# HMC830_CLK_DIST.net
KiCad netlist of a schematic drawn in Altium Designer
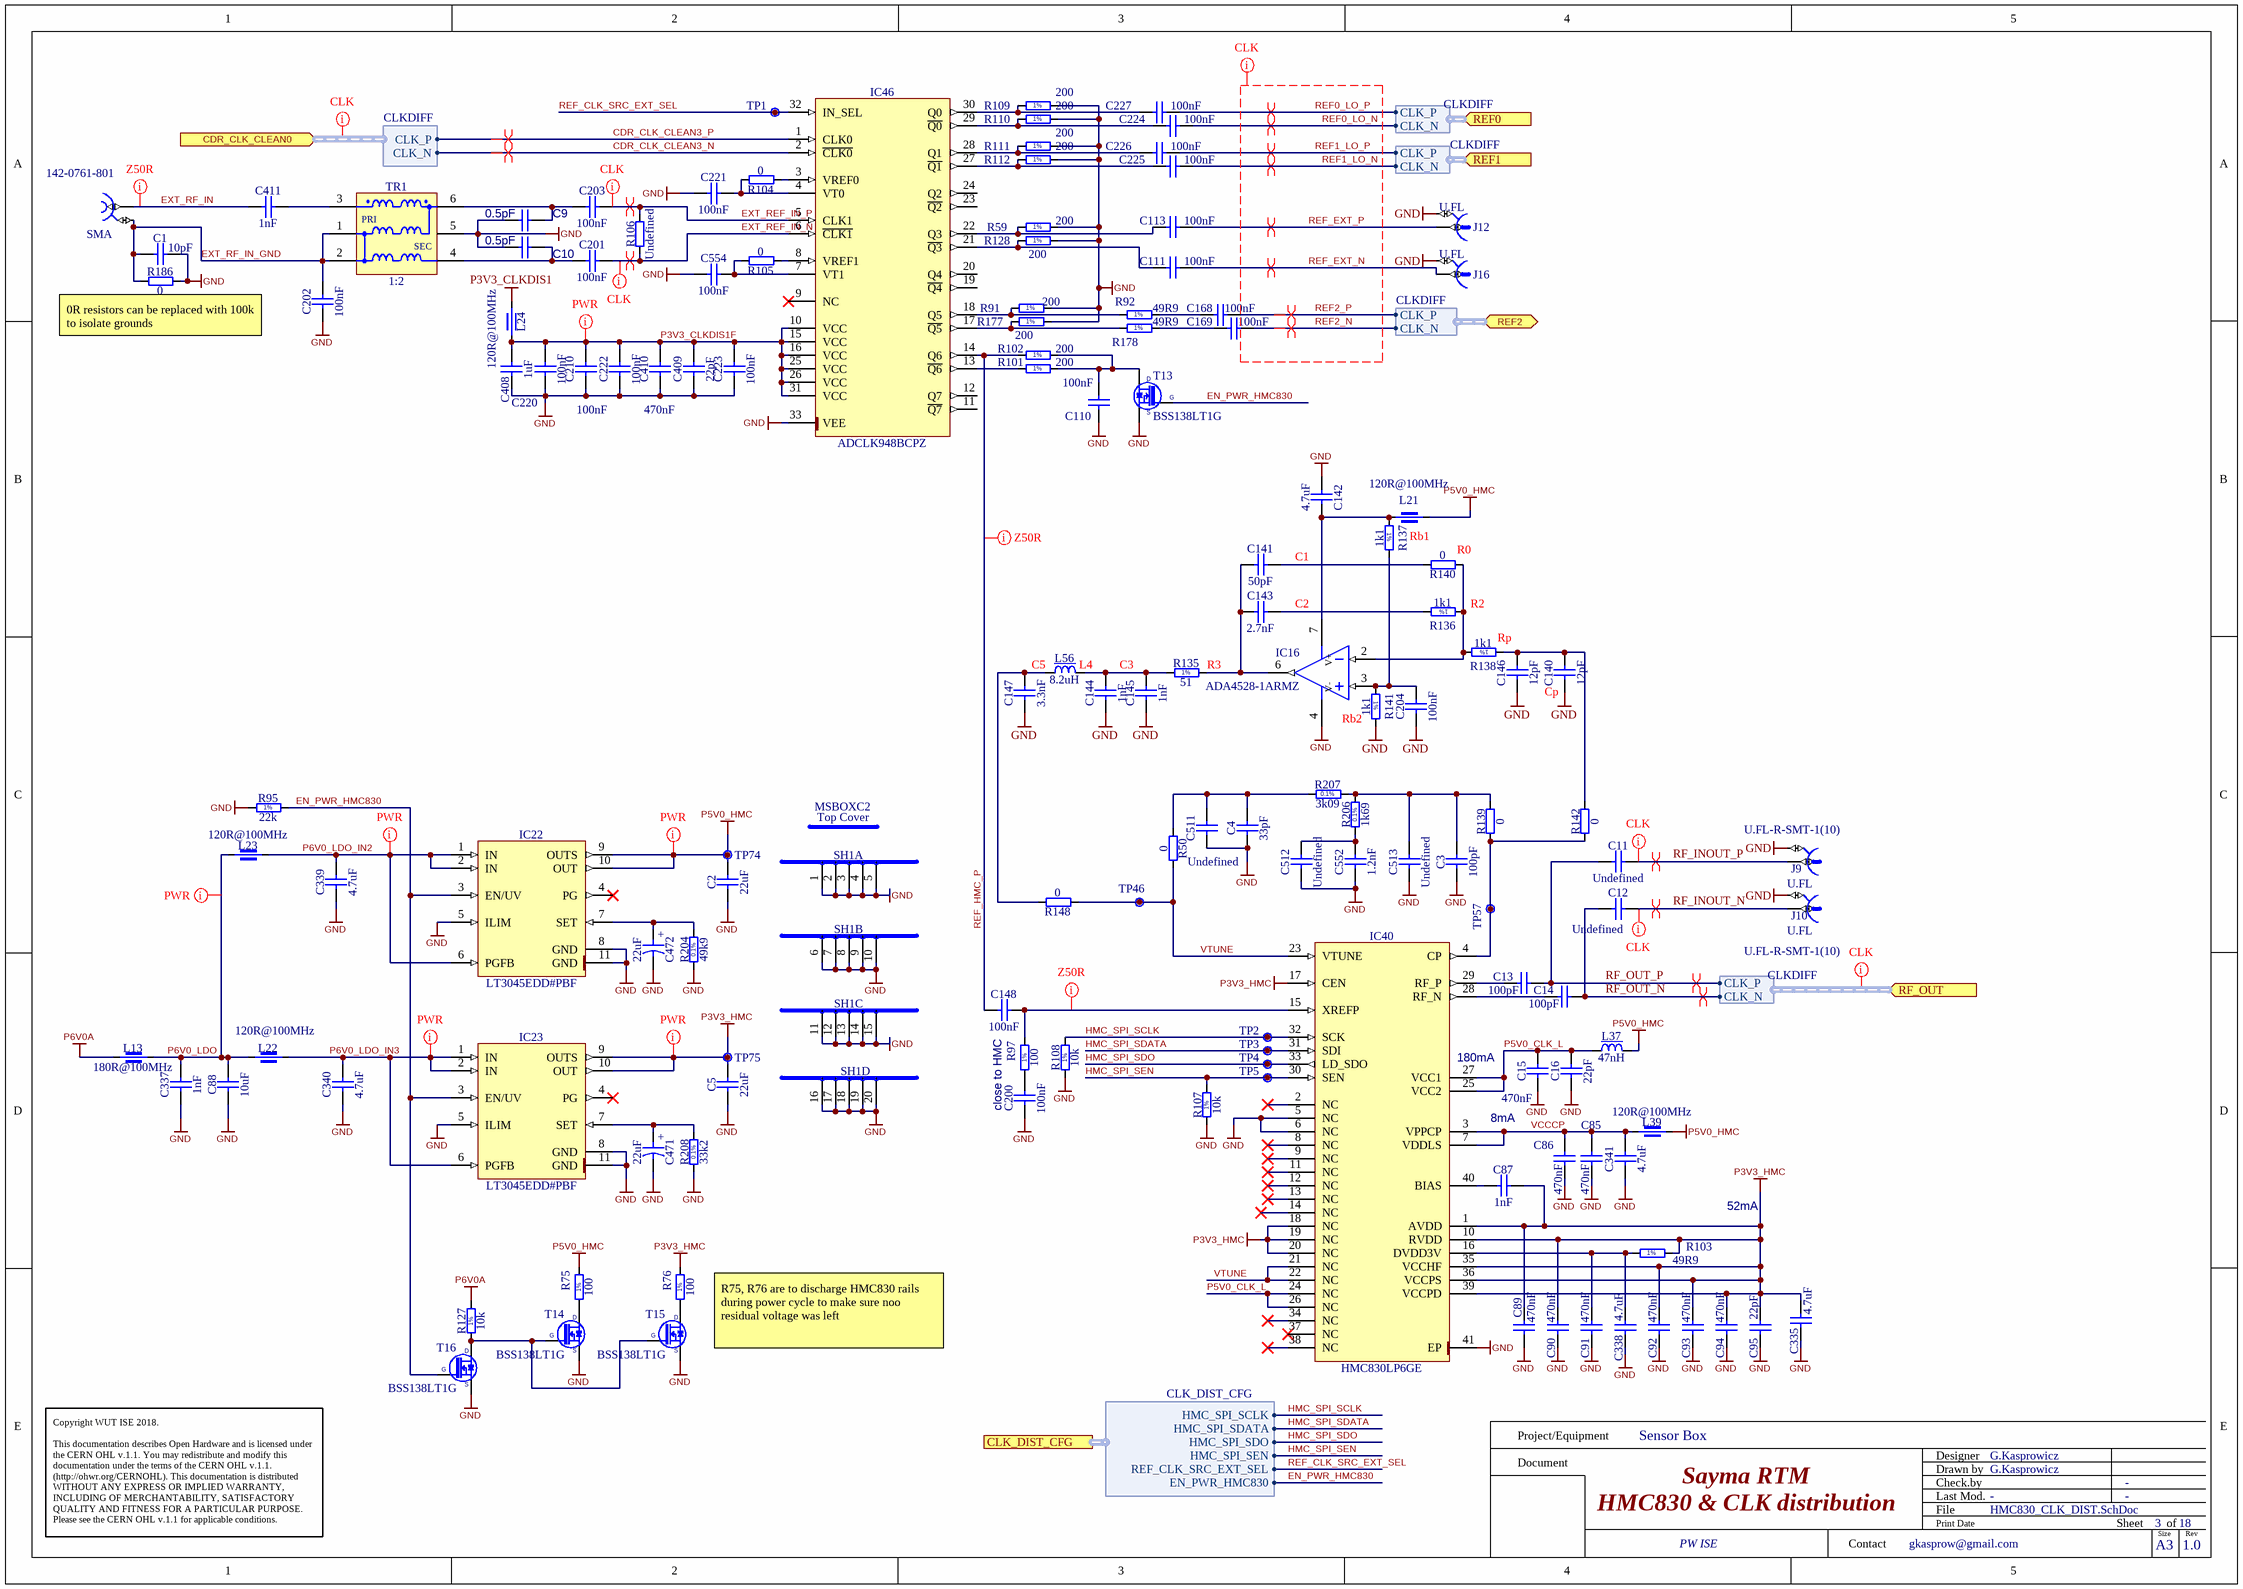
[diagram p0: HMC830_CLK_DIST.SchDoc]

(export (version "E")
  (design (tool "Eeschema 10.0.6"))
  (components
    (comp (ref "C1")
      (value "10pF")
      (footprint "CAPC1608X87N")
      (description "Non-polarised capacitor")
      (fields
        (field (name "MANUFACTURER PART NUMBER") "CC0603_10PF_50V_5%_NP0")
        (field (name "MANUFACTURER") "GENERIC")
        (field (name "AUTHOR") "CERN DEM JLC")
      )
      (libsource (lib "Capacitors") (part "Capacitor - non polarized"))
    )
    (comp (ref "C2")
      (value "22uF")
      (footprint "CAPC2012X135N")
      (description "Non-polarised capacitor")
      (fields
        (field (name "MANUFACTURER PART NUMBER") "CC0805_22UF_16V_10%_X5R")
        (field (name "MANUFACTURER") "GENERIC")
        (field (name "AUTHOR") "CERN DEM JLC")
      )
      (libsource (lib "Capacitors") (part "Capacitor - non polarized"))
    )
    (comp (ref "C3")
      (value "100pF")
      (footprint "CAPC1608X87N")
      (description "Non-polarised capacitor")
      (fields
        (field (name "MANUFACTURER PART NUMBER") "CC0603_100PF_50V_5%_NP0")
        (field (name "MANUFACTURER") "GENERIC")
        (field (name "AUTHOR") "CERN DEM JLC")
      )
      (libsource (lib "Capacitors") (part "Capacitor - non polarized"))
    )
    (comp (ref "C4")
      (value "33pF")
      (footprint "CAPC1608X87N")
      (description "Non-polarised capacitor")
      (fields
        (field (name "MANUFACTURER PART NUMBER") "CC0603_33PF_50V_5%_NP0")
        (field (name "MANUFACTURER") "GENERIC")
        (field (name "AUTHOR") "CERN DEM JLC")
      )
      (libsource (lib "Capacitors") (part "Capacitor - non polarized"))
    )
    (comp (ref "C5")
      (value "22uF")
      (footprint "CAPC2012X135N")
      (description "Non-polarised capacitor")
      (fields
        (field (name "MANUFACTURER PART NUMBER") "CC0805_22UF_16V_10%_X5R")
        (field (name "MANUFACTURER") "GENERIC")
        (field (name "AUTHOR") "CERN DEM JLC")
      )
      (libsource (lib "Capacitors") (part "Capacitor - non polarized"))
    )
    (comp (ref "C9")
      (value "0.5pF")
      (footprint "CAPC1005X55N")
      (fields
        (field (name "$$NOTCOMMONPROPERTY_GENERAL PART NUMBER") "CC0402_0.5PF_25V_0.25PF_C0G")
        (field (name "MANUFACTURER PART NUMBER") "CC0402_0.5PF_25V_0.05PF_C0G")
        (field (name "MANUFACTURER") "GENERIC")
      )
      (libsource (lib "altium-import") (part "root_0__*"))
    )
    (comp (ref "C10")
      (value "0.5pF")
      (footprint "CAPC1005X55N")
      (fields
        (field (name "$$NOTCOMMONPROPERTY_GENERAL PART NUMBER") "CC0402_0.5PF_25V_0.25PF_C0G")
        (field (name "MANUFACTURER PART NUMBER") "CC0402_0.5PF_25V_0.05PF_C0G")
        (field (name "MANUFACTURER") "GENERIC")
      )
      (libsource (lib "altium-import") (part "root_0__*"))
    )
    (comp (ref "C11")
      (value "Undefined")
      (footprint "CAPC1005X55N")
      (description "Non-polarised capacitor")
      (fields (field (name "PART NUMBER") "CC0402_NO-VALUE") (field (name "AUTHOR") "CERN DEM JLC"))
      (libsource (lib "Capacitors") (part "Capacitor - non polarized"))
    )
    (comp (ref "C12")
      (value "Undefined")
      (footprint "CAPC1005X55N")
      (description "Non-polarised capacitor")
      (fields (field (name "PART NUMBER") "CC0402_NO-VALUE") (field (name "AUTHOR") "CERN DEM JLC"))
      (libsource (lib "Capacitors") (part "Capacitor - non polarized"))
    )
    (comp (ref "C13")
      (value "100pF")
      (footprint "CAPC1608X87N")
      (description "Non-polarised capacitor")
      (fields
        (field (name "MANUFACTURER PART NUMBER") "CC0603_100PF_50V_5%_NP0")
        (field (name "MANUFACTURER") "GENERIC")
        (field (name "AUTHOR") "CERN DEM JLC")
      )
      (libsource (lib "Capacitors") (part "Capacitor - non polarized"))
    )
    (comp (ref "C14")
      (value "100pF")
      (footprint "CAPC1608X87N")
      (description "Non-polarised capacitor")
      (fields
        (field (name "MANUFACTURER PART NUMBER") "CC0603_100PF_50V_5%_NP0")
        (field (name "MANUFACTURER") "GENERIC")
        (field (name "AUTHOR") "CERN DEM JLC")
      )
      (libsource (lib "Capacitors") (part "Capacitor - non polarized"))
    )
    (comp (ref "C15")
      (value "470nF")
      (footprint "CAPC1005X55N")
      (description "Non-polarised capacitor")
      (fields
        (field (name "MANUFACTURER PART NUMBER") "CC0402_470NF_16V_10%_X5R")
        (field (name "MANUFACTURER") "GENERIC")
        (field (name "AUTHOR") "CERN DEM JLC")
      )
      (libsource (lib "Capacitors") (part "Capacitor - non polarized"))
    )
    (comp (ref "C16")
      (value "22pF")
      (footprint "CAPC1005X55N")
      (description "Non-polarised capacitor")
      (fields
        (field (name "MANUFACTURER PART NUMBER") "CC0402_22PF_50V_5%_C0G")
        (field (name "MANUFACTURER") "GENERIC")
        (field (name "AUTHOR") "CERN DEM JLC")
      )
      (libsource (lib "Capacitors") (part "Capacitor - non polarized"))
    )
    (comp (ref "C85")
      (value "470nF")
      (footprint "CAPC1005X55N")
      (description "Non-polarised capacitor")
      (fields
        (field (name "MANUFACTURER PART NUMBER") "CC0402_470NF_16V_10%_X5R")
        (field (name "MANUFACTURER") "GENERIC")
        (field (name "AUTHOR") "CERN DEM JLC")
      )
      (libsource (lib "Capacitors") (part "Capacitor - non polarized"))
    )
    (comp (ref "C86")
      (value "470nF")
      (footprint "CAPC1005X55N")
      (description "Non-polarised capacitor")
      (fields
        (field (name "MANUFACTURER PART NUMBER") "CC0402_470NF_16V_10%_X5R")
        (field (name "MANUFACTURER") "GENERIC")
        (field (name "AUTHOR") "CERN DEM JLC")
      )
      (libsource (lib "Capacitors") (part "Capacitor - non polarized"))
    )
    (comp (ref "C87")
      (value "1nF")
      (footprint "CAPC1005X55N")
      (description "Non-polarised capacitor")
      (fields
        (field (name "MANUFACTURER PART NUMBER") "CC0402_1NF_50V_10%_X7R")
        (field (name "MANUFACTURER") "GENERIC")
        (field (name "AUTHOR") "CERN DEM JLC")
      )
      (libsource (lib "Capacitors") (part "Capacitor - non polarized"))
    )
    (comp (ref "C88")
      (value "10uF")
      (footprint "CAPC3216X180N")
      (description "Non-polarised capacitor")
      (fields
        (field (name "MANUFACTURER PART NUMBER") "CC1206_10uF_25V_10%_X7R")
        (field (name "MANUFACTURER") "GENERIC")
        (field (name "AUTHOR") "CERN DEM JLC")
      )
      (libsource (lib "Capacitors") (part "Capacitor - non polarized"))
    )
    (comp (ref "C89")
      (value "470nF")
      (footprint "CAPC1005X55N")
      (description "Non-polarised capacitor")
      (fields
        (field (name "MANUFACTURER PART NUMBER") "CC0402_470NF_16V_10%_X5R")
        (field (name "MANUFACTURER") "GENERIC")
        (field (name "AUTHOR") "CERN DEM JLC")
      )
      (libsource (lib "Capacitors") (part "Capacitor - non polarized"))
    )
    (comp (ref "C90")
      (value "470nF")
      (footprint "CAPC1005X55N")
      (description "Non-polarised capacitor")
      (fields
        (field (name "MANUFACTURER PART NUMBER") "CC0402_470NF_16V_10%_X5R")
        (field (name "MANUFACTURER") "GENERIC")
        (field (name "AUTHOR") "CERN DEM JLC")
      )
      (libsource (lib "Capacitors") (part "Capacitor - non polarized"))
    )
    (comp (ref "C91")
      (value "470nF")
      (footprint "CAPC1005X55N")
      (description "Non-polarised capacitor")
      (fields
        (field (name "MANUFACTURER PART NUMBER") "CC0402_470NF_16V_10%_X5R")
        (field (name "MANUFACTURER") "GENERIC")
        (field (name "AUTHOR") "CERN DEM JLC")
      )
      (libsource (lib "Capacitors") (part "Capacitor - non polarized"))
    )
    (comp (ref "C92")
      (value "470nF")
      (footprint "CAPC1005X55N")
      (description "Non-polarised capacitor")
      (fields
        (field (name "MANUFACTURER PART NUMBER") "CC0402_470NF_16V_10%_X5R")
        (field (name "MANUFACTURER") "GENERIC")
        (field (name "AUTHOR") "CERN DEM JLC")
      )
      (libsource (lib "Capacitors") (part "Capacitor - non polarized"))
    )
    (comp (ref "C93")
      (value "470nF")
      (footprint "CAPC1005X55N")
      (description "Non-polarised capacitor")
      (fields
        (field (name "MANUFACTURER PART NUMBER") "CC0402_470NF_16V_10%_X5R")
        (field (name "MANUFACTURER") "GENERIC")
        (field (name "AUTHOR") "CERN DEM JLC")
      )
      (libsource (lib "Capacitors") (part "Capacitor - non polarized"))
    )
    (comp (ref "C94")
      (value "470nF")
      (footprint "CAPC1005X55N")
      (description "Non-polarised capacitor")
      (fields
        (field (name "MANUFACTURER PART NUMBER") "CC0402_470NF_16V_10%_X5R")
        (field (name "MANUFACTURER") "GENERIC")
        (field (name "AUTHOR") "CERN DEM JLC")
      )
      (libsource (lib "Capacitors") (part "Capacitor - non polarized"))
    )
    (comp (ref "C95")
      (value "22pF")
      (footprint "CAPC1005X55N")
      (description "Non-polarised capacitor")
      (fields
        (field (name "MANUFACTURER PART NUMBER") "CC0402_22PF_50V_5%_C0G")
        (field (name "MANUFACTURER") "GENERIC")
        (field (name "AUTHOR") "CERN DEM JLC")
      )
      (libsource (lib "Capacitors") (part "Capacitor - non polarized"))
    )
    (comp (ref "C110")
      (value "100nF")
      (footprint "CAPC0603X33N")
      (description "Non-polarised capacitor")
      (fields
        (field (name "MANUFACTURER PART NUMBER") "CC0201_100NF_6.3V_10%_X5R")
        (field (name "MANUFACTURER") "GENERIC")
        (field (name "AUTHOR") "CERN DEM JLC")
      )
      (libsource (lib "Capacitors") (part "Capacitor - non polarized"))
    )
    (comp (ref "C111")
      (value "100nF")
      (footprint "CAPC0603X33N")
      (description "Non-polarised capacitor")
      (fields
        (field (name "MANUFACTURER PART NUMBER") "CC0201_100NF_6.3V_10%_X5R")
        (field (name "MANUFACTURER") "GENERIC")
        (field (name "AUTHOR") "CERN DEM JLC")
      )
      (libsource (lib "Capacitors") (part "Capacitor - non polarized"))
    )
    (comp (ref "C113")
      (value "100nF")
      (footprint "CAPC0603X33N")
      (description "Non-polarised capacitor")
      (fields
        (field (name "MANUFACTURER PART NUMBER") "CC0201_100NF_6.3V_10%_X5R")
        (field (name "MANUFACTURER") "GENERIC")
        (field (name "AUTHOR") "CERN DEM JLC")
      )
      (libsource (lib "Capacitors") (part "Capacitor - non polarized"))
    )
    (comp (ref "C140")
      (value "12pF")
      (footprint "CAPC1608X87N")
      (description "Non-polarised capacitor")
      (fields
        (field (name "PART NUMBER") "CC0603_12PF_50V_5%_NP0")
        (field (name "VOLTAGE") "50V")
        (field (name "AUTHOR") "CERN DEM JLC")
      )
      (libsource (lib "Capacitors") (part "Capacitor - non polarized"))
    )
    (comp (ref "C141")
      (value "50pF")
      (footprint "CAPC1608X90N")
      (description "Non-polarised capacitor")
      (fields
        (field (name "PART NUMBER") "CC0603_50PF_50V_5%_NP0")
        (field (name "VOLTAGE") "50V")
        (field (name "AUTHOR") "CERN DEM JLC")
      )
      (libsource (lib "Capacitors") (part "Capacitor - non polarized"))
    )
    (comp (ref "C142")
      (value "4.7uF")
      (footprint "CAPC1608X90N")
      (description "Non-polarised capacitor")
      (fields
        (field (name "MANUFACTURER PART NUMBER") "CC0603_4.7UF_25V_10%_X5R")
        (field (name "MANUFACTURER") "GENERIC")
        (field (name "AUTHOR") "CERN DEM JLC")
      )
      (libsource (lib "Capacitors") (part "Capacitor - non polarized"))
    )
    (comp (ref "C143")
      (value "2.7nF")
      (footprint "CAPC3216X140N")
      (description "Non-polarised capacitor")
      (fields
        (field (name "PART NUMBER") "CC1206_2.7NF_100V_1%_NP0")
        (field (name "VOLTAGE") "100V")
        (field (name "AUTHOR") "CERN DEM JLC")
      )
      (libsource (lib "Capacitors") (part "Capacitor - non polarized"))
    )
    (comp (ref "C144")
      (value "1nF")
      (footprint "CAPC1608X90N")
      (description "Non-polarised capacitor")
      (fields
        (field (name "PART NUMBER") "CC0603_1NF_50V_1%_NP0")
        (field (name "VOLTAGE") "50V")
        (field (name "AUTHOR") "CERN DEM JLC")
      )
      (libsource (lib "Capacitors") (part "Capacitor - non polarized"))
    )
    (comp (ref "C145")
      (value "1nF")
      (footprint "CAPC1608X90N")
      (description "Non-polarised capacitor")
      (fields
        (field (name "PART NUMBER") "CC0603_1NF_50V_1%_NP0")
        (field (name "VOLTAGE") "50V")
        (field (name "AUTHOR") "CERN DEM JLC")
      )
      (libsource (lib "Capacitors") (part "Capacitor - non polarized"))
    )
    (comp (ref "C146")
      (value "12pF")
      (footprint "CAPC1608X87N")
      (description "Non-polarised capacitor")
      (fields
        (field (name "PART NUMBER") "CC0603_12PF_50V_5%_NP0")
        (field (name "VOLTAGE") "50V")
        (field (name "AUTHOR") "CERN DEM JLC")
      )
      (libsource (lib "Capacitors") (part "Capacitor - non polarized"))
    )
    (comp (ref "C147")
      (value "3.3nF")
      (footprint "CAPC1608X87N")
      (description "Non-polarised capacitor")
      (fields
        (field (name "PART NUMBER") "CC0603_3.3NF_50V_10%_X7R")
        (field (name "VOLTAGE") "50V")
        (field (name "AUTHOR") "CERN DEM JLC")
      )
      (libsource (lib "Capacitors") (part "Capacitor - non polarized"))
    )
    (comp (ref "C148")
      (value "100nF")
      (footprint "CAPC0603X33N")
      (description "Non-polarised capacitor")
      (fields
        (field (name "MANUFACTURER PART NUMBER") "CC0201_100NF_6.3V_10%_X5R")
        (field (name "MANUFACTURER") "GENERIC")
        (field (name "AUTHOR") "CERN DEM JLC")
      )
      (libsource (lib "Capacitors") (part "Capacitor - non polarized"))
    )
    (comp (ref "C168")
      (value "100nF")
      (footprint "CAPC0603X33N")
      (description "Non-polarised capacitor")
      (fields
        (field (name "MANUFACTURER PART NUMBER") "CC0201_100NF_6.3V_10%_X5R")
        (field (name "MANUFACTURER") "GENERIC")
        (field (name "AUTHOR") "CERN DEM JLC")
      )
      (libsource (lib "Capacitors") (part "Capacitor - non polarized"))
    )
    (comp (ref "C169")
      (value "100nF")
      (footprint "CAPC0603X33N")
      (description "Non-polarised capacitor")
      (fields
        (field (name "MANUFACTURER PART NUMBER") "CC0201_100NF_6.3V_10%_X5R")
        (field (name "MANUFACTURER") "GENERIC")
        (field (name "AUTHOR") "CERN DEM JLC")
      )
      (libsource (lib "Capacitors") (part "Capacitor - non polarized"))
    )
    (comp (ref "C200")
      (value "100nF")
      (footprint "CAPC0603X33N")
      (description "Non-polarised capacitor")
      (fields
        (field (name "MANUFACTURER PART NUMBER") "CC0201_100NF_6.3V_10%_X5R")
        (field (name "MANUFACTURER") "GENERIC")
        (field (name "AUTHOR") "CERN DEM JLC")
      )
      (libsource (lib "Capacitors") (part "Capacitor - non polarized"))
    )
    (comp (ref "C201")
      (value "100nF")
      (footprint "CAPC0603X33N")
      (description "Non-polarised capacitor")
      (fields
        (field (name "MANUFACTURER PART NUMBER") "CC0201_100NF_6.3V_10%_X5R")
        (field (name "MANUFACTURER") "GENERIC")
        (field (name "AUTHOR") "CERN DEM JLC")
      )
      (libsource (lib "Capacitors") (part "Capacitor - non polarized"))
    )
    (comp (ref "C202")
      (value "100nF")
      (footprint "CAPC0603X33N")
      (description "Non-polarised capacitor")
      (fields
        (field (name "MANUFACTURER PART NUMBER") "CC0201_100NF_6.3V_10%_X5R")
        (field (name "MANUFACTURER") "GENERIC")
        (field (name "AUTHOR") "CERN DEM JLC")
      )
      (libsource (lib "Capacitors") (part "Capacitor - non polarized"))
    )
    (comp (ref "C203")
      (value "100nF")
      (footprint "CAPC0603X33N")
      (description "Non-polarised capacitor")
      (fields
        (field (name "MANUFACTURER PART NUMBER") "CC0201_100NF_6.3V_10%_X5R")
        (field (name "MANUFACTURER") "GENERIC")
        (field (name "AUTHOR") "CERN DEM JLC")
      )
      (libsource (lib "Capacitors") (part "Capacitor - non polarized"))
    )
    (comp (ref "C204")
      (value "100nF")
      (footprint "CAPC0603X33N")
      (description "Non-polarised capacitor")
      (fields
        (field (name "MANUFACTURER PART NUMBER") "CC0201_100NF_6.3V_10%_X5R")
        (field (name "MANUFACTURER") "GENERIC")
        (field (name "AUTHOR") "CERN DEM JLC")
      )
      (libsource (lib "Capacitors") (part "Capacitor - non polarized"))
    )
    (comp (ref "C210")
      (value "100nF")
      (footprint "CAPC0603X33N")
      (description "Non-polarised capacitor")
      (fields
        (field (name "MANUFACTURER PART NUMBER") "CC0201_100NF_6.3V_10%_X5R")
        (field (name "MANUFACTURER") "GENERIC")
        (field (name "AUTHOR") "CERN DEM JLC")
      )
      (libsource (lib "Capacitors") (part "Capacitor - non polarized"))
    )
    (comp (ref "C220")
      (value "100nF")
      (footprint "CAPC0603X33N")
      (description "Non-polarised capacitor")
      (fields
        (field (name "MANUFACTURER PART NUMBER") "CC0201_100NF_6.3V_10%_X5R")
        (field (name "MANUFACTURER") "GENERIC")
        (field (name "AUTHOR") "CERN DEM JLC")
      )
      (libsource (lib "Capacitors") (part "Capacitor - non polarized"))
    )
    (comp (ref "C221")
      (value "100nF")
      (footprint "CAPC0603X33N")
      (description "Non-polarised capacitor")
      (fields
        (field (name "MANUFACTURER PART NUMBER") "CC0201_100NF_6.3V_10%_X5R")
        (field (name "MANUFACTURER") "GENERIC")
        (field (name "AUTHOR") "CERN DEM JLC")
      )
      (libsource (lib "Capacitors") (part "Capacitor - non polarized"))
    )
    (comp (ref "C222")
      (value "100nF")
      (footprint "CAPC0603X33N")
      (description "Non-polarised capacitor")
      (fields
        (field (name "MANUFACTURER PART NUMBER") "CC0201_100NF_6.3V_10%_X5R")
        (field (name "MANUFACTURER") "GENERIC")
        (field (name "AUTHOR") "CERN DEM JLC")
      )
      (libsource (lib "Capacitors") (part "Capacitor - non polarized"))
    )
    (comp (ref "C223")
      (value "100nF")
      (footprint "CAPC0603X33N")
      (description "Non-polarised capacitor")
      (fields
        (field (name "MANUFACTURER PART NUMBER") "CC0201_100NF_6.3V_10%_X5R")
        (field (name "MANUFACTURER") "GENERIC")
        (field (name "AUTHOR") "CERN DEM JLC")
      )
      (libsource (lib "Capacitors") (part "Capacitor - non polarized"))
    )
    (comp (ref "C224")
      (value "100nF")
      (footprint "CAPC0603X33N")
      (description "Non-polarised capacitor")
      (fields
        (field (name "MANUFACTURER PART NUMBER") "CC0201_100NF_6.3V_10%_X5R")
        (field (name "MANUFACTURER") "GENERIC")
        (field (name "AUTHOR") "CERN DEM JLC")
      )
      (libsource (lib "Capacitors") (part "Capacitor - non polarized"))
    )
    (comp (ref "C225")
      (value "100nF")
      (footprint "CAPC0603X33N")
      (description "Non-polarised capacitor")
      (fields
        (field (name "MANUFACTURER PART NUMBER") "CC0201_100NF_6.3V_10%_X5R")
        (field (name "MANUFACTURER") "GENERIC")
        (field (name "AUTHOR") "CERN DEM JLC")
      )
      (libsource (lib "Capacitors") (part "Capacitor - non polarized"))
    )
    (comp (ref "C226")
      (value "100nF")
      (footprint "CAPC0603X33N")
      (description "Non-polarised capacitor")
      (fields
        (field (name "MANUFACTURER PART NUMBER") "CC0201_100NF_6.3V_10%_X5R")
        (field (name "MANUFACTURER") "GENERIC")
        (field (name "AUTHOR") "CERN DEM JLC")
      )
      (libsource (lib "Capacitors") (part "Capacitor - non polarized"))
    )
    (comp (ref "C227")
      (value "100nF")
      (footprint "CAPC0603X33N")
      (description "Non-polarised capacitor")
      (fields
        (field (name "MANUFACTURER PART NUMBER") "CC0201_100NF_6.3V_10%_X5R")
        (field (name "MANUFACTURER") "GENERIC")
        (field (name "AUTHOR") "CERN DEM JLC")
      )
      (libsource (lib "Capacitors") (part "Capacitor - non polarized"))
    )
    (comp (ref "C335")
      (value "4.7uF")
      (footprint "CAPC1608X90N")
      (description "Non-polarised capacitor")
      (fields
        (field (name "MANUFACTURER PART NUMBER") "CC0603_4.7UF_25V_10%_X5R")
        (field (name "MANUFACTURER") "GENERIC")
        (field (name "AUTHOR") "CERN DEM JLC")
      )
      (libsource (lib "Capacitors") (part "Capacitor - non polarized"))
    )
    (comp (ref "C337")
      (value "1nF")
      (footprint "CAPC1608X90N")
      (description "Non-polarised capacitor")
      (fields
        (field (name "MANUFACTURER PART NUMBER") "CC0603_1NF_50V_5%_NP0")
        (field (name "MANUFACTURER") "GENERIC")
        (field (name "AUTHOR") "CERN DEM JLC")
      )
      (libsource (lib "Capacitors") (part "Capacitor - non polarized"))
    )
    (comp (ref "C338")
      (value "4.7uF")
      (footprint "CAPC1608X90N")
      (description "Non-polarised capacitor")
      (fields
        (field (name "MANUFACTURER PART NUMBER") "CC0603_4.7UF_25V_10%_X5R")
        (field (name "MANUFACTURER") "GENERIC")
        (field (name "AUTHOR") "CERN DEM JLC")
      )
      (libsource (lib "Capacitors") (part "Capacitor - non polarized"))
    )
    (comp (ref "C339")
      (value "4.7uF")
      (footprint "CAPC1608X90N")
      (description "Non-polarised capacitor")
      (fields
        (field (name "MANUFACTURER PART NUMBER") "CC0603_4.7UF_25V_10%_X5R")
        (field (name "MANUFACTURER") "GENERIC")
        (field (name "AUTHOR") "CERN DEM JLC")
      )
      (libsource (lib "Capacitors") (part "Capacitor - non polarized"))
    )
    (comp (ref "C340")
      (value "4.7uF")
      (footprint "CAPC1608X90N")
      (description "Non-polarised capacitor")
      (fields
        (field (name "MANUFACTURER PART NUMBER") "CC0603_4.7UF_25V_10%_X5R")
        (field (name "MANUFACTURER") "GENERIC")
        (field (name "AUTHOR") "CERN DEM JLC")
      )
      (libsource (lib "Capacitors") (part "Capacitor - non polarized"))
    )
    (comp (ref "C341")
      (value "4.7uF")
      (footprint "CAPC1608X90N")
      (description "Non-polarised capacitor")
      (fields
        (field (name "MANUFACTURER PART NUMBER") "CC0603_4.7UF_25V_10%_X5R")
        (field (name "MANUFACTURER") "GENERIC")
        (field (name "AUTHOR") "CERN DEM JLC")
      )
      (libsource (lib "Capacitors") (part "Capacitor - non polarized"))
    )
    (comp (ref "C408")
      (value "1uF")
      (footprint "CAPC1005X55N")
      (description "Non-polarised capacitor")
      (fields
        (field (name "MANUFACTURER PART NUMBER") "CC0402_1UF_16V_10%_X5R")
        (field (name "MANUFACTURER") "GENERIC")
        (field (name "AUTHOR") "CERN DEM JLC")
      )
      (libsource (lib "Capacitors") (part "Capacitor - non polarized"))
    )
    (comp (ref "C409")
      (value "22pF")
      (footprint "CAPC1005X55N")
      (description "Non-polarised capacitor")
      (fields
        (field (name "MANUFACTURER PART NUMBER") "CC0402_22PF_50V_5%_C0G")
        (field (name "MANUFACTURER") "GENERIC")
        (field (name "AUTHOR") "CERN DEM JLC")
      )
      (libsource (lib "Capacitors") (part "Capacitor - non polarized"))
    )
    (comp (ref "C410")
      (value "470nF")
      (footprint "CAPC1005X55N")
      (description "Non-polarised capacitor")
      (fields
        (field (name "MANUFACTURER PART NUMBER") "CC0402_470NF_16V_10%_X5R")
        (field (name "MANUFACTURER") "GENERIC")
        (field (name "AUTHOR") "CERN DEM JLC")
      )
      (libsource (lib "Capacitors") (part "Capacitor - non polarized"))
    )
    (comp (ref "C411")
      (value "1nF")
      (footprint "CAPC1005X55N")
      (description "Non-polarised capacitor")
      (fields
        (field (name "MANUFACTURER PART NUMBER") "CC0402_1NF_50V_10%_X7R")
        (field (name "MANUFACTURER") "GENERIC")
        (field (name "AUTHOR") "CERN DEM JLC")
      )
      (libsource (lib "Capacitors") (part "Capacitor - non polarized"))
    )
    (comp (ref "C471")
      (value "22uF")
      (footprint "CAPMP3216X180N")
      (description "Polarised capacitor")
      (fields
        (field (name "MANUFACTURER PART NUMBER") "CTE3216-18_22UF_6.3V_10%_LESR0900")
        (field (name "MANUFACTURER") "GENERIC")
        (field (name "AUTHOR") "CERN DEM JLC")
      )
      (libsource (lib "Capacitors") (part "Capacitor - polarized"))
    )
    (comp (ref "C472")
      (value "22uF")
      (footprint "CAPMP3216X180N")
      (description "Polarised capacitor")
      (fields
        (field (name "MANUFACTURER PART NUMBER") "CTE3216-18_22UF_6.3V_10%_LESR0900")
        (field (name "MANUFACTURER") "GENERIC")
        (field (name "AUTHOR") "CERN DEM JLC")
      )
      (libsource (lib "Capacitors") (part "Capacitor - polarized"))
    )
    (comp (ref "C511")
      (value "Undefined")
      (footprint "CAPC2012X135N")
      (description "Non-polarised capacitor")
      (fields
        (field (name "MANUFACTURER PART NUMBER") "CC0805_NO-VALUE")
        (field (name "AUTHOR") "CERN DEM JLC")
      )
      (libsource (lib "Capacitors") (part "Capacitor - non polarized"))
    )
    (comp (ref "C512")
      (value "Undefined")
      (footprint "CAPC2012X135N")
      (description "Non-polarised capacitor")
      (fields
        (field (name "MANUFACTURER PART NUMBER") "CC0805_NO-VALUE")
        (field (name "AUTHOR") "CERN DEM JLC")
      )
      (libsource (lib "Capacitors") (part "Capacitor - non polarized"))
    )
    (comp (ref "C513")
      (value "Undefined")
      (footprint "CAPC2012X135N")
      (description "Non-polarised capacitor")
      (fields
        (field (name "MANUFACTURER PART NUMBER") "CC0805_NO-VALUE")
        (field (name "AUTHOR") "CERN DEM JLC")
      )
      (libsource (lib "Capacitors") (part "Capacitor - non polarized"))
    )
    (comp (ref "C552")
      (value "1.2nF")
      (footprint "CAPC3216X140N")
      (description "Non-polarised capacitor")
      (fields
        (field (name "MANUFACTURER PART NUMBER") "CC1206_1.2NF_50V_5%_NP0")
        (field (name "MANUFACTURER") "GENERIC")
        (field (name "AUTHOR") "CERN DEM JLC")
      )
      (libsource (lib "Capacitors") (part "Capacitor - non polarized"))
    )
    (comp (ref "C554")
      (value "100nF")
      (footprint "CAPC0603X33N")
      (description "Non-polarised capacitor")
      (fields
        (field (name "MANUFACTURER PART NUMBER") "CC0201_100NF_6.3V_10%_X5R")
        (field (name "MANUFACTURER") "GENERIC")
        (field (name "AUTHOR") "CERN DEM JLC")
      )
      (libsource (lib "Capacitors") (part "Capacitor - non polarized"))
    )
    (comp (ref "IC16")
      (value "ADA4528-1ARMZ")
      (footprint "SOP65P490X110-8N")
      (description "Operational Amplifier")
      (fields (field (name "MANUFACTURER") "ANALOG DEVICES") (field (name "AUTHOR") "CERN DEM JLC"))
      (libsource (lib "ICs And Semiconductors") (part "Operational Amplifier Type1"))
    )
    (comp (ref "IC22")
      (value "LT3045EDD#PBF")
      (footprint "SON50P300X300X80-11N-R175X248")
      (description "20V, 500mA, Ultralow Noise, Ultrahigh PSRR Linear Regulator")
      (fields (field (name "MANUFACTURER") "LINEAR TECHNOLOGY") (field (name "AUTHOR") "CERN DEM JLC"))
      (libsource (lib "ICs And Semiconductors") (part "LT3045EDD"))
    )
    (comp (ref "IC23")
      (value "LT3045EDD#PBF")
      (footprint "SON50P300X300X80-11N-R175X248")
      (description "20V, 500mA, Ultralow Noise, Ultrahigh PSRR Linear Regulator")
      (fields (field (name "MANUFACTURER") "LINEAR TECHNOLOGY") (field (name "AUTHOR") "CERN DEM JLC"))
      (libsource (lib "ICs And Semiconductors") (part "LT3045EDD"))
    )
    (comp (ref "IC40")
      (value "HMC830LP6GE")
      (footprint "QFN50P600X600X90-41N-S475")
      (description "Fractional-N PLL With Integrated VCO, 25 to 3000MHz")
      (fields (field (name "MANUFACTURER") "HITTITE MICROWAVE CORP") (field (name "AUTHOR") "CERN DEM JMW"))
      (libsource (lib "ICs And Semiconductors") (part "HMC830LP6GE"))
    )
    (comp (ref "IC46")
      (value "ADCLK948BCPZ")
      (footprint "QFN50P500X500X80-33N-S285")
      (description "Two Selectable Inputs, 8 LVPECL Outputs, SiGe Clock Fanout Buffer")
      (fields (field (name "MANUFACTURER") "ANALOG DEVICES") (field (name "AUTHOR") "CERN DEM MR"))
      (libsource (lib "ICs And Semiconductors") (part "ADCLK948"))
    )
    (comp (ref "J4")
      (value "SMA")
      (footprint "CINCH_142-0761-801")
      (fields
        (field (name "FAMILY") "SMA")
        (field (name "MANUFACTURER PART NUMBER") "142-0761-801")
        (field (name "MANUFACTURER") "CINCH CONNECTIVITY")
        (field (name "PART NUMBER") "CINCH_142-0761-801")
        (field (name "AUTHOR") "CERN DEM JLC")
      )
      (libsource (lib "Connectors") (part "Coax_1Female_1Shield"))
    )
    (comp (ref "J9")
      (value "U.FL")
      (footprint "HIROSE_U.FL-R-SMT-1(10)")
      (fields
        (field (name "FAMILY") "U.FL")
        (field (name "MANUFACTURER PART NUMBER") "U.FL-R-SMT-1(10)")
        (field (name "MANUFACTURER") "HIROSE (HRS)")
        (field (name "PART NUMBER") "HIROSE_U.FL-R-SMT-1(10)")
        (field (name "AUTHOR") "CERN DEM JLC")
      )
      (libsource (lib "Connectors") (part "Coax_1Male_1Shield"))
    )
    (comp (ref "J10")
      (value "U.FL")
      (footprint "HIROSE_U.FL-R-SMT-1(10)")
      (fields
        (field (name "FAMILY") "U.FL")
        (field (name "MANUFACTURER PART NUMBER") "U.FL-R-SMT-1(10)")
        (field (name "MANUFACTURER") "HIROSE (HRS)")
        (field (name "PART NUMBER") "HIROSE_U.FL-R-SMT-1(10)")
        (field (name "AUTHOR") "CERN DEM JLC")
      )
      (libsource (lib "Connectors") (part "Coax_1Male_1Shield"))
    )
    (comp (ref "J12")
      (value "U.FL")
      (footprint "HIROSE_U.FL-R-SMT-1(10)")
      (fields
        (field (name "MANUFACTURER PART NUMBER") "U.FL-R-SMT-1(10)")
        (field (name "MANUFACTURER") "HIROSE (HRS)")
        (field (name "PART NUMBER") "HIROSE_U.FL-R-SMT-1(10)")
        (field (name "AUTHOR") "CERN DEM JLC")
      )
      (libsource (lib "Connectors") (part "Coax_1Male_1Shield"))
    )
    (comp (ref "J16")
      (value "U.FL")
      (footprint "HIROSE_U.FL-R-SMT-1(10)")
      (fields
        (field (name "MANUFACTURER PART NUMBER") "U.FL-R-SMT-1(10)")
        (field (name "MANUFACTURER") "HIROSE (HRS)")
        (field (name "PART NUMBER") "HIROSE_U.FL-R-SMT-1(10)")
        (field (name "AUTHOR") "CERN DEM JLC")
      )
      (libsource (lib "Connectors") (part "Coax_1Male_1Shield"))
    )
    (comp (ref "L13")
      (value "180R@100MHz")
      (footprint "INDC4516X180N")
      (fields
        (field (name "MANUFACTURER PART NUMBER") "BLM41PG181SN1L")
        (field (name "MANUFACTURER") "MURATA")
        (field (name "PART NUMBER") "IND1806_MURATA_BLM41PG181SN1L")
        (field (name "AUTHOR") "CERN DEM JLC")
      )
      (libsource (lib "Inductors & Transformers") (part "Ferrite Bead"))
    )
    (comp (ref "L21")
      (value "120R@100MHz")
      (footprint "INDC1608X95N")
      (fields
        (field (name "MANUFACTURER PART NUMBER") "BLM18PG121SN1D")
        (field (name "MANUFACTURER") "MURATA")
        (field (name "PART NUMBER") "IND0603_MURATA_BLM18PG121SN1D")
        (field (name "AUTHOR") "CERN DEM BC")
      )
      (libsource (lib "Inductors & Transformers") (part "Ferrite Bead"))
    )
    (comp (ref "L22")
      (value "120R@100MHz")
      (footprint "INDC1608X95N")
      (fields
        (field (name "MANUFACTURER PART NUMBER") "BLM18PG121SN1D")
        (field (name "MANUFACTURER") "MURATA")
        (field (name "PART NUMBER") "IND0603_MURATA_BLM18PG121SN1D")
        (field (name "AUTHOR") "CERN DEM BC")
      )
      (libsource (lib "Inductors & Transformers") (part "Ferrite Bead"))
    )
    (comp (ref "L23")
      (value "120R@100MHz")
      (footprint "INDC1608X95N")
      (fields
        (field (name "MANUFACTURER PART NUMBER") "BLM18PG121SN1D")
        (field (name "MANUFACTURER") "MURATA")
        (field (name "PART NUMBER") "IND0603_MURATA_BLM18PG121SN1D")
        (field (name "AUTHOR") "CERN DEM BC")
      )
      (libsource (lib "Inductors & Transformers") (part "Ferrite Bead"))
    )
    (comp (ref "L24")
      (value "120R@100MHz")
      (footprint "INDC1608X95N")
      (fields
        (field (name "MANUFACTURER PART NUMBER") "BLM18PG121SN1D")
        (field (name "MANUFACTURER") "MURATA")
        (field (name "PART NUMBER") "IND0603_MURATA_BLM18PG121SN1D")
        (field (name "AUTHOR") "CERN DEM BC")
      )
      (libsource (lib "") (part "Ferrite Bead_1"))
    )
    (comp (ref "L37")
      (value "47nH")
      (footprint "INDC2014X145N")
      (description "Inductor With Core")
      (fields
        (field (name "MANUFACTURER PART NUMBER") "B82498B3470J")
        (field (name "MANUFACTURER") "EPCOS")
        (field (name "AUTHOR") "CERN DEM JLC")
      )
      (libsource (lib "Inductors & Transformers") (part "Inductor With Magnetic core"))
    )
    (comp (ref "L39")
      (value "120R@100MHz")
      (footprint "INDC1608X95N")
      (fields
        (field (name "MANUFACTURER PART NUMBER") "BLM18PG121SN1D")
        (field (name "MANUFACTURER") "MURATA")
        (field (name "PART NUMBER") "IND0603_MURATA_BLM18PG121SN1D")
        (field (name "AUTHOR") "CERN DEM BC")
      )
      (libsource (lib "Inductors & Transformers") (part "Ferrite Bead"))
    )
    (comp (ref "L56")
      (value "8.2uH")
      (footprint "IND_COILCRAFT_0603LS")
      (description "Inductor With Core")
      (fields
        (field (name "PART NUMBER") "IND_8.2UH_2%_COILCRAFT_0603LS")
        (field (name "POWER") "190mA")
        (field (name "AUTHOR") "GK")
      )
      (libsource (lib "LIBRARY_SCH") (part "L_0603_8.2uH"))
    )
    (comp (ref "MSBOXC2")
      (value "Top Cover")
      (footprint "MSBOX_WURTH_36003300")
      (description "Metal Screening Box - Top Cover 0 Pin")
      (fields
        (field (name "PART NUMBER") "MSBOX_WURTH_36003300")
        (field (name "MANUFACTURER") "WURTH")
        (field (name "AUTHOR") "CERN DEM JLC")
      )
      (libsource (lib "Eletro-mechanical") (part "Metal Screening Box - Top Cover"))
    )
    (comp (ref "R50")
      (value "0")
      (footprint "RESC1608X55N")
      (description "Resistor")
      (fields
        (field (name "PART NUMBER") "R0603_0R_JUMPER")
        (field (name "MANUFACTURER") "GENERIC")
        (field (name "AUTHOR") "CERN DEM JLC")
      )
      (libsource (lib "Resistors") (part "Resistor"))
    )
    (comp (ref "R59")
      (value "200")
      (footprint "RESC1005X40N")
      (description "Resistor - 1%")
      (fields
        (field (name "MANUFACTURER PART NUMBER") "R0402_200R_1%_0.0625W_100PPM")
        (field (name "MANUFACTURER") "GENERIC")
        (field (name "AUTHOR") "CERN DEM JLC")
      )
      (libsource (lib "Resistors") (part "Resistor - 1%"))
    )
    (comp (ref "R75")
      (value "100")
      (footprint "RESC1005X40N")
      (description "Resistor - 1%")
      (fields
        (field (name "MANUFACTURER PART NUMBER") "R0402_100R_1%_0.0625W_100PPM")
        (field (name "MANUFACTURER") "GENERIC")
        (field (name "AUTHOR") "CERN DEM JLC")
      )
      (libsource (lib "Resistors") (part "Resistor - 1%"))
    )
    (comp (ref "R76")
      (value "100")
      (footprint "RESC1005X40N")
      (description "Resistor - 1%")
      (fields
        (field (name "MANUFACTURER PART NUMBER") "R0402_100R_1%_0.0625W_100PPM")
        (field (name "MANUFACTURER") "GENERIC")
        (field (name "AUTHOR") "CERN DEM JLC")
      )
      (libsource (lib "Resistors") (part "Resistor - 1%"))
    )
    (comp (ref "R91")
      (value "200")
      (footprint "RESC1005X40N")
      (description "Resistor - 1%")
      (fields
        (field (name "MANUFACTURER PART NUMBER") "R0402_200R_1%_0.0625W_100PPM")
        (field (name "MANUFACTURER") "GENERIC")
        (field (name "AUTHOR") "CERN DEM JLC")
      )
      (libsource (lib "Resistors") (part "Resistor - 1%"))
    )
    (comp (ref "R92")
      (value "49R9")
      (footprint "RESC1005X40N")
      (description "Resistor - 1%")
      (fields
        (field (name "MANUFACTURER PART NUMBER") "R0402_49R9_1%_0.0625W_100PPM")
        (field (name "MANUFACTURER") "GENERIC")
        (field (name "AUTHOR") "CERN DEM JLC")
      )
      (libsource (lib "Resistors") (part "Resistor - 1%"))
    )
    (comp (ref "R95")
      (value "22k")
      (footprint "RESC1005X40N")
      (description "Resistor - 1%")
      (fields
        (field (name "MANUFACTURER PART NUMBER") "R0402_22K_1%_0.0625W_100PPM")
        (field (name "MANUFACTURER") "GENERIC")
        (field (name "AUTHOR") "CERN DEM JLC")
      )
      (libsource (lib "Resistors") (part "Resistor - 1%"))
    )
    (comp (ref "R97")
      (value "100")
      (footprint "RESC1005X40N")
      (description "Resistor - 1%")
      (fields
        (field (name "MANUFACTURER PART NUMBER") "R0402_100R_1%_0.0625W_100PPM")
        (field (name "MANUFACTURER") "GENERIC")
        (field (name "AUTHOR") "CERN DEM JLC")
      )
      (libsource (lib "Resistors") (part "Resistor - 1%"))
    )
    (comp (ref "R101")
      (value "200")
      (footprint "RESC1005X40N")
      (description "Resistor - 1%")
      (fields
        (field (name "MANUFACTURER PART NUMBER") "R0402_200R_1%_0.0625W_100PPM")
        (field (name "MANUFACTURER") "GENERIC")
        (field (name "AUTHOR") "CERN DEM JLC")
      )
      (libsource (lib "Resistors") (part "Resistor - 1%"))
    )
    (comp (ref "R102")
      (value "200")
      (footprint "RESC1005X40N")
      (description "Resistor - 1%")
      (fields
        (field (name "MANUFACTURER PART NUMBER") "R0402_200R_1%_0.0625W_100PPM")
        (field (name "MANUFACTURER") "GENERIC")
        (field (name "AUTHOR") "CERN DEM JLC")
      )
      (libsource (lib "Resistors") (part "Resistor - 1%"))
    )
    (comp (ref "R103")
      (value "49R9")
      (footprint "RESC1005X40N")
      (description "Resistor - 1%")
      (fields
        (field (name "MANUFACTURER PART NUMBER") "R0402_49R9_1%_0.0625W_100PPM")
        (field (name "MANUFACTURER") "GENERIC")
        (field (name "AUTHOR") "CERN DEM JLC")
      )
      (libsource (lib "Resistors") (part "Resistor - 1%"))
    )
    (comp (ref "R104")
      (value "0")
      (footprint "RESC1005X40N")
      (description "Resistor")
      (fields
        (field (name "MANUFACTURER PART NUMBER") "R0402_0R_JUMPER")
        (field (name "MANUFACTURER") "GENERIC")
        (field (name "AUTHOR") "CERN DEM JLC")
      )
      (libsource (lib "Resistors") (part "Resistor"))
    )
    (comp (ref "R105")
      (value "0")
      (footprint "RESC1005X40N")
      (description "Resistor")
      (fields
        (field (name "MANUFACTURER PART NUMBER") "R0402_0R_JUMPER")
        (field (name "MANUFACTURER") "GENERIC")
        (field (name "AUTHOR") "CERN DEM JLC")
      )
      (libsource (lib "Resistors") (part "Resistor"))
    )
    (comp (ref "R106")
      (value "Undefined")
      (footprint "RESC1005X40N")
      (description "Resistor")
      (fields
        (field (name "MANUFACTURER PART NUMBER") "R0402_NO-VALUE")
        (field (name "AUTHOR") "CERN DEM JLC")
      )
      (libsource (lib "Resistors") (part "Resistor"))
    )
    (comp (ref "R107")
      (value "10k")
      (footprint "RESC1005X40N")
      (description "Resistor - 1%")
      (fields
        (field (name "MANUFACTURER PART NUMBER") "R0402_10K_1%_0.0625W_100PPM")
        (field (name "MANUFACTURER") "GENERIC")
        (field (name "AUTHOR") "CERN DEM JLC")
      )
      (libsource (lib "Resistors") (part "Resistor - 1%"))
    )
    (comp (ref "R108")
      (value "10k")
      (footprint "RESC1005X40N")
      (description "Resistor - 1%")
      (fields
        (field (name "MANUFACTURER PART NUMBER") "R0402_10K_1%_0.0625W_100PPM")
        (field (name "MANUFACTURER") "GENERIC")
        (field (name "AUTHOR") "CERN DEM JLC")
      )
      (libsource (lib "Resistors") (part "Resistor - 1%"))
    )
    (comp (ref "R109")
      (value "200")
      (footprint "RESC1005X40N")
      (description "Resistor - 1%")
      (fields
        (field (name "MANUFACTURER PART NUMBER") "R0402_200R_1%_0.0625W_100PPM")
        (field (name "MANUFACTURER") "GENERIC")
        (field (name "AUTHOR") "CERN DEM JLC")
      )
      (libsource (lib "Resistors") (part "Resistor - 1%"))
    )
    (comp (ref "R110")
      (value "200")
      (footprint "RESC1005X40N")
      (description "Resistor - 1%")
      (fields
        (field (name "MANUFACTURER PART NUMBER") "R0402_200R_1%_0.0625W_100PPM")
        (field (name "MANUFACTURER") "GENERIC")
        (field (name "AUTHOR") "CERN DEM JLC")
      )
      (libsource (lib "Resistors") (part "Resistor - 1%"))
    )
    (comp (ref "R111")
      (value "200")
      (footprint "RESC1005X40N")
      (description "Resistor - 1%")
      (fields
        (field (name "MANUFACTURER PART NUMBER") "R0402_200R_1%_0.0625W_100PPM")
        (field (name "MANUFACTURER") "GENERIC")
        (field (name "AUTHOR") "CERN DEM JLC")
      )
      (libsource (lib "Resistors") (part "Resistor - 1%"))
    )
    (comp (ref "R112")
      (value "200")
      (footprint "RESC1005X40N")
      (description "Resistor - 1%")
      (fields
        (field (name "MANUFACTURER PART NUMBER") "R0402_200R_1%_0.0625W_100PPM")
        (field (name "MANUFACTURER") "GENERIC")
        (field (name "AUTHOR") "CERN DEM JLC")
      )
      (libsource (lib "Resistors") (part "Resistor - 1%"))
    )
    (comp (ref "R127")
      (value "10k")
      (footprint "RESC1005X40N")
      (description "Resistor - 1%")
      (fields
        (field (name "MANUFACTURER PART NUMBER") "R0402_10K_1%_0.0625W_100PPM")
        (field (name "MANUFACTURER") "GENERIC")
        (field (name "AUTHOR") "CERN DEM JLC")
      )
      (libsource (lib "Resistors") (part "Resistor - 1%"))
    )
    (comp (ref "R128")
      (value "200")
      (footprint "RESC1005X40N")
      (description "Resistor - 1%")
      (fields
        (field (name "MANUFACTURER PART NUMBER") "R0402_200R_1%_0.0625W_100PPM")
        (field (name "MANUFACTURER") "GENERIC")
        (field (name "AUTHOR") "CERN DEM JLC")
      )
      (libsource (lib "Resistors") (part "Resistor - 1%"))
    )
    (comp (ref "R135")
      (value "51")
      (footprint "RESC1608X55N")
      (description "Resistor - 1%")
      (fields
        (field (name "PART NUMBER") "R0603_51R_1%_0.1W_100PPM")
        (field (name "POWER") "0.1W")
        (field (name "AUTHOR") "CERN DEM JLC")
      )
      (libsource (lib "Resistors") (part "Resistor - 1%"))
    )
    (comp (ref "R136")
      (value "1k1")
      (footprint "RESC1608X55N")
      (description "Resistor - 1%")
      (fields
        (field (name "PART NUMBER") "R0603_1K1_1%_0.1W_100PPM")
        (field (name "POWER") "0.1W")
        (field (name "AUTHOR") "CERN DEM JLC")
      )
      (libsource (lib "Resistors") (part "Resistor - 1%"))
    )
    (comp (ref "R137")
      (value "1k1")
      (footprint "RESC1608X55N")
      (description "Resistor - 1%")
      (fields
        (field (name "PART NUMBER") "R0603_1K1_1%_0.1W_100PPM")
        (field (name "POWER") "0.1W")
        (field (name "AUTHOR") "CERN DEM JLC")
      )
      (libsource (lib "Resistors") (part "Resistor - 1%"))
    )
    (comp (ref "R138")
      (value "1k1")
      (footprint "RESC1608X55N")
      (description "Resistor - 1%")
      (fields
        (field (name "PART NUMBER") "R0603_1K1_1%_0.1W_100PPM")
        (field (name "POWER") "0.1W")
        (field (name "AUTHOR") "CERN DEM JLC")
      )
      (libsource (lib "Resistors") (part "Resistor - 1%"))
    )
    (comp (ref "R139")
      (value "0")
      (footprint "RESC1608X55N")
      (description "Resistor")
      (fields
        (field (name "PART NUMBER") "R0603_0R_JUMPER")
        (field (name "MANUFACTURER") "GENERIC")
        (field (name "AUTHOR") "CERN DEM JLC")
      )
      (libsource (lib "Resistors") (part "Resistor"))
    )
    (comp (ref "R140")
      (value "0")
      (footprint "RESC1608X55N")
      (description "Resistor")
      (fields
        (field (name "PART NUMBER") "R0603_0R_JUMPER")
        (field (name "MANUFACTURER") "GENERIC")
        (field (name "AUTHOR") "CERN DEM JLC")
      )
      (libsource (lib "Resistors") (part "Resistor"))
    )
    (comp (ref "R141")
      (value "1k1")
      (footprint "RESC1608X55N")
      (description "Resistor - 1%")
      (fields
        (field (name "PART NUMBER") "R0603_1K1_1%_0.1W_100PPM")
        (field (name "POWER") "0.1W")
        (field (name "AUTHOR") "CERN DEM JLC")
      )
      (libsource (lib "Resistors") (part "Resistor - 1%"))
    )
    (comp (ref "R142")
      (value "0")
      (footprint "RESC1608X55N")
      (description "Resistor")
      (fields
        (field (name "PART NUMBER") "R0603_0R_JUMPER")
        (field (name "MANUFACTURER") "GENERIC")
        (field (name "AUTHOR") "CERN DEM JLC")
      )
      (libsource (lib "Resistors") (part "Resistor"))
    )
    (comp (ref "R148")
      (value "0")
      (footprint "RESC1608X55N")
      (description "Resistor")
      (fields
        (field (name "PART NUMBER") "R0603_0R_JUMPER")
        (field (name "MANUFACTURER") "GENERIC")
        (field (name "AUTHOR") "CERN DEM JLC")
      )
      (libsource (lib "Resistors") (part "Resistor"))
    )
    (comp (ref "R177")
      (value "200")
      (footprint "RESC1005X40N")
      (description "Resistor - 1%")
      (fields
        (field (name "MANUFACTURER PART NUMBER") "R0402_200R_1%_0.0625W_100PPM")
        (field (name "MANUFACTURER") "GENERIC")
        (field (name "AUTHOR") "CERN DEM JLC")
      )
      (libsource (lib "Resistors") (part "Resistor - 1%"))
    )
    (comp (ref "R178")
      (value "49R9")
      (footprint "RESC1005X40N")
      (description "Resistor - 1%")
      (fields
        (field (name "MANUFACTURER PART NUMBER") "R0402_49R9_1%_0.0625W_100PPM")
        (field (name "MANUFACTURER") "GENERIC")
        (field (name "AUTHOR") "CERN DEM JLC")
      )
      (libsource (lib "Resistors") (part "Resistor - 1%"))
    )
    (comp (ref "R186")
      (value "0")
      (footprint "RESC1005X40N")
      (description "Resistor")
      (fields
        (field (name "MANUFACTURER PART NUMBER") "R0402_0R_JUMPER")
        (field (name "MANUFACTURER") "GENERIC")
        (field (name "AUTHOR") "CERN DEM JLC")
      )
      (libsource (lib "Resistors") (part "Resistor"))
    )
    (comp (ref "R204")
      (value "49k9")
      (footprint "RESC1608X55N")
      (description "Resistor - 0.1%")
      (fields
        (field (name "MANUFACTURER PART NUMBER") "R0603_49K9_0.1%_0.063W_10PPM")
        (field (name "MANUFACTURER") "GENERIC")
        (field (name "AUTHOR") "CERN DEM JLC")
      )
      (libsource (lib "Resistors") (part "Resistor - 0.1%"))
    )
    (comp (ref "R206")
      (value "1k69")
      (footprint "RESC1608X55N")
      (description "Resistor - 0.1%")
      (fields
        (field (name "MANUFACTURER PART NUMBER") "R0603_1K69_0.1%_0.063W_10PPM")
        (field (name "MANUFACTURER") "GENERIC")
        (field (name "AUTHOR") "CERN DEM JLC")
      )
      (libsource (lib "Resistors") (part "Resistor - 0.1%"))
    )
    (comp (ref "R207")
      (value "3k09")
      (footprint "RESC1608X55N")
      (description "Resistor - 0.1%")
      (fields
        (field (name "MANUFACTURER PART NUMBER") "R0603_3K09_0.1%_0.063W_10PPM")
        (field (name "MANUFACTURER") "GENERIC")
        (field (name "AUTHOR") "CERN DEM JLC")
      )
      (libsource (lib "Resistors") (part "Resistor - 0.1%"))
    )
    (comp (ref "R208")
      (value "33k2")
      (footprint "RESC1608X55N")
      (description "Resistor - 0.1%")
      (fields
        (field (name "MANUFACTURER PART NUMBER") "R0603_33K2_0.1%_0.063W_10PPM")
        (field (name "MANUFACTURER") "GENERIC")
        (field (name "AUTHOR") "CERN DEM JLC")
      )
      (libsource (lib "Resistors") (part "Resistor - 0.1%"))
    )
    (comp (ref "SH1")
      (value "Metal Screening Box 4x5 Pins")
      (footprint "MSBOX_WURTH_36103305")
      (description "Metal Screening Box 20 (4x5) Pins")
      (fields
        (field (name "MANUFACTURER PART NUMBER") "36103305")
        (field (name "MANUFACTURER") "WURTH")
        (field (name "AUTHOR") "CERN DEM JLC")
      )
      (libsource (lib "Eletro-mechanical") (part "Metal Screening Box - 4x5 pins"))
    )
    (comp (ref "T13")
      (value "BSS138LT1G")
      (footprint "SOT95P240X110-3N")
      (description "N-CHANNEL MOSFET WITH DIODE")
      (fields (field (name "MANUFACTURER") "ON SEMICONDUCTOR") (field (name "AUTHOR") "CERN DEM JLC"))
      (libsource (lib "") (part "N-MOSFET-D 1G 2S 3D_1"))
    )
    (comp (ref "T14")
      (value "BSS138LT1G")
      (footprint "SOT95P240X110-3N")
      (description "N-CHANNEL MOSFET WITH DIODE")
      (fields (field (name "MANUFACTURER") "ON SEMICONDUCTOR") (field (name "AUTHOR") "CERN DEM JLC"))
      (libsource (lib "ICs And Semiconductors") (part "N-MOSFET-D 1G 2S 3D"))
    )
    (comp (ref "T15")
      (value "BSS138LT1G")
      (footprint "SOT95P240X110-3N")
      (description "N-CHANNEL MOSFET WITH DIODE")
      (fields (field (name "MANUFACTURER") "ON SEMICONDUCTOR") (field (name "AUTHOR") "CERN DEM JLC"))
      (libsource (lib "ICs And Semiconductors") (part "N-MOSFET-D 1G 2S 3D"))
    )
    (comp (ref "T16")
      (value "BSS138LT1G")
      (footprint "SOT95P240X110-3N")
      (description "N-CHANNEL MOSFET WITH DIODE")
      (fields (field (name "MANUFACTURER") "ON SEMICONDUCTOR") (field (name "AUTHOR") "CERN DEM JLC"))
      (libsource (lib "ICs And Semiconductors") (part "N-MOSFET-D 1G 2S 3D"))
    )
    (comp (ref "TP1")
      (value "Test Point")
      (footprint "TPS127")
      (fields (field (name "PART NUMBER") "SMD_PAD_1.27X1.27MM") (field (name "AUTHOR") "CERN DEM JLC"))
      (libsource (lib "Eletro-mechanical") (part "Test Point"))
    )
    (comp (ref "TP2")
      (value "Test Point")
      (footprint "TPS127")
      (fields (field (name "PART NUMBER") "SMD_PAD_1.27X1.27MM") (field (name "AUTHOR") "CERN DEM JLC"))
      (libsource (lib "Eletro-mechanical") (part "Test Point"))
    )
    (comp (ref "TP3")
      (value "Test Point")
      (footprint "TPS127")
      (fields (field (name "PART NUMBER") "SMD_PAD_1.27X1.27MM") (field (name "AUTHOR") "CERN DEM JLC"))
      (libsource (lib "Eletro-mechanical") (part "Test Point"))
    )
    (comp (ref "TP4")
      (value "Test Point")
      (footprint "TPS127")
      (fields (field (name "PART NUMBER") "SMD_PAD_1.27X1.27MM") (field (name "AUTHOR") "CERN DEM JLC"))
      (libsource (lib "Eletro-mechanical") (part "Test Point"))
    )
    (comp (ref "TP5")
      (value "Test Point")
      (footprint "TPS127")
      (fields (field (name "PART NUMBER") "SMD_PAD_1.27X1.27MM") (field (name "AUTHOR") "CERN DEM JLC"))
      (libsource (lib "Eletro-mechanical") (part "Test Point"))
    )
    (comp (ref "TP46")
      (value "Test Point")
      (footprint "TPS127")
      (fields (field (name "PART NUMBER") "SMD_PAD_1.27X1.27MM") (field (name "AUTHOR") "CERN DEM JLC"))
      (libsource (lib "Eletro-mechanical") (part "Test Point"))
    )
    (comp (ref "TP57")
      (value "Test Point")
      (footprint "TPS127")
      (fields (field (name "PART NUMBER") "SMD_PAD_1.27X1.27MM") (field (name "AUTHOR") "CERN DEM JLC"))
      (libsource (lib "Eletro-mechanical") (part "Test Point"))
    )
    (comp (ref "TP74")
      (value "Test Point")
      (footprint "TPS127")
      (fields (field (name "PART NUMBER") "SMD_PAD_1.27X1.27MM") (field (name "AUTHOR") "CERN DEM JLC"))
      (libsource (lib "Eletro-mechanical") (part "Test Point"))
    )
    (comp (ref "TP75")
      (value "Test Point")
      (footprint "TPS127")
      (fields (field (name "PART NUMBER") "SMD_PAD_1.27X1.27MM") (field (name "AUTHOR") "CERN DEM JLC"))
      (libsource (lib "Eletro-mechanical") (part "Test Point"))
    )
    (comp (ref "TR1")
      (value "1:2")
      (footprint "XFMR_MINI-CIRCUITS_DB1627")
      (description "50 OHMS 10 to 4000 MHz RF Transformer")
      (fields
        (field (name "MANUFACTURER PART NUMBER") "TCM2-43X+")
        (field (name "MANUFACTURER") "MINI-CIRCUITS")
        (field (name "AUTHOR") "CERN DEM BC")
      )
      (libsource (lib "Inductors & Transformers") (part "XFMR_MINI-CIRCUITS_TCM2-43X"))
    )
  )
  (nets
    (net (code "3") (name "/CDR_CLK_CLEAN3_N") (class "Default")
      (node (ref "IC46") (pin "2") (pinfunction "~{CLK0}_2") (pintype "input"))
    )
    (net (code "4") (name "/CDR_CLK_CLEAN3_P") (class "Default")
      (node (ref "IC46") (pin "1") (pinfunction "CLK0_1") (pintype "input"))
    )
    (net (code "5") (name "/EN_PWR_HMC830") (class "Default")
      (node (ref "IC22") (pin "3") (pinfunction "EN/UV_3") (pintype "input"))
      (node (ref "IC23") (pin "3") (pinfunction "EN/UV_3") (pintype "input"))
      (node (ref "R95") (pin "2") (pinfunction "2_2") (pintype "passive"))
      (node (ref "T13") (pin "1") (pinfunction "G_1") (pintype "passive"))
      (node (ref "T16") (pin "1") (pinfunction "G_1") (pintype "passive"))
    )
    (net (code "6") (name "/EXT_REF_IN_N") (class "Default")
      (node (ref "C201") (pin "2") (pinfunction "2_2") (pintype "passive"))
      (node (ref "IC46") (pin "6") (pinfunction "~{CLK1}_6") (pintype "input"))
      (node (ref "R106") (pin "1") (pinfunction "1_1") (pintype "passive"))
    )
    (net (code "7") (name "/EXT_REF_IN_P") (class "Default")
      (node (ref "C203") (pin "2") (pinfunction "2_2") (pintype "passive"))
      (node (ref "IC46") (pin "5") (pinfunction "CLK1_5") (pintype "input"))
      (node (ref "R106") (pin "2") (pinfunction "2_2") (pintype "passive"))
    )
    (net (code "8") (name "/EXT_RF_IN") (class "Default")
      (node (ref "C411") (pin "1") (pinfunction "1_1") (pintype "passive"))
      (node (ref "J4") (pin "1") (pinfunction "1_1") (pintype "bidirectional"))
    )
    (net (code "9") (name "/EXT_RF_IN_GND") (class "Default")
      (node (ref "C1") (pin "1") (pinfunction "1_1") (pintype "passive"))
      (node (ref "C202") (pin "2") (pinfunction "2_2") (pintype "passive"))
      (node (ref "J4") (pin "2") (pinfunction "2_2") (pintype "bidirectional"))
      (node (ref "R186") (pin "1") (pinfunction "1_1") (pintype "passive"))
      (node (ref "TR1") (pin "1") (pinfunction "P1_1") (pintype "passive"))
      (node (ref "TR1") (pin "2") (pinfunction "P1_2") (pintype "passive"))
    )
    (net (code "10") (name "/HMC_SPI_SCLK") (class "Default")
      (node (ref "IC40") (pin "32") (pinfunction "SCK_32") (pintype "input"))
      (node (ref "R108") (pin "2") (pinfunction "2_2") (pintype "passive"))
      (node (ref "TP2") (pin "1") (pinfunction "1_1") (pintype "bidirectional"))
    )
    (net (code "11") (name "/HMC_SPI_SDATA") (class "Default")
      (node (ref "IC40") (pin "31") (pinfunction "SDI_31") (pintype "input"))
      (node (ref "TP3") (pin "1") (pinfunction "1_1") (pintype "bidirectional"))
    )
    (net (code "12") (name "/HMC_SPI_SDO") (class "Default")
      (node (ref "IC40") (pin "33") (pinfunction "LD_SDO_33") (pintype "output"))
      (node (ref "TP4") (pin "1") (pinfunction "1_1") (pintype "bidirectional"))
    )
    (net (code "13") (name "/HMC_SPI_SEN") (class "Default")
      (node (ref "IC40") (pin "30") (pinfunction "SEN_30") (pintype "input"))
      (node (ref "R107") (pin "2") (pinfunction "2_2") (pintype "passive"))
      (node (ref "TP5") (pin "1") (pinfunction "1_1") (pintype "bidirectional"))
    )
    (net (code "14") (name "/P3V3_CLKDIS1F") (class "Default")
      (node (ref "C210") (pin "2") (pinfunction "2_2") (pintype "passive"))
      (node (ref "C220") (pin "2") (pinfunction "2_2") (pintype "passive"))
      (node (ref "C222") (pin "2") (pinfunction "2_2") (pintype "passive"))
      (node (ref "C223") (pin "2") (pinfunction "2_2") (pintype "passive"))
      (node (ref "C408") (pin "1") (pinfunction "1_1") (pintype "passive"))
      (node (ref "C409") (pin "2") (pinfunction "2_2") (pintype "passive"))
      (node (ref "C410") (pin "2") (pinfunction "2_2") (pintype "passive"))
      (node (ref "IC46") (pin "10") (pinfunction "VCC_10") (pintype "power_in"))
      (node (ref "IC46") (pin "15") (pinfunction "VCC_15") (pintype "power_in"))
      (node (ref "IC46") (pin "16") (pinfunction "VCC_16") (pintype "power_in"))
      (node (ref "IC46") (pin "25") (pinfunction "VCC_25") (pintype "power_in"))
      (node (ref "IC46") (pin "26") (pinfunction "VCC_26") (pintype "power_in"))
      (node (ref "IC46") (pin "31") (pinfunction "VCC_31") (pintype "power_in"))
      (node (ref "L24") (pin "2") (pinfunction "2_2") (pintype "passive"))
    )
    (net (code "15") (name "/P5V0_CLK_L") (class "Default")
      (node (ref "C15") (pin "2") (pinfunction "2_2") (pintype "passive"))
      (node (ref "C16") (pin "2") (pinfunction "2_2") (pintype "passive"))
      (node (ref "IC40") (pin "24") (pinfunction "NC_24") (pintype "passive"))
      (node (ref "IC40") (pin "25") (pinfunction "VCC2_25") (pintype "power_in"))
      (node (ref "IC40") (pin "26") (pinfunction "NC_26") (pintype "passive"))
      (node (ref "IC40") (pin "27") (pinfunction "VCC1_27") (pintype "power_in"))
      (node (ref "L37") (pin "1") (pinfunction "1_1") (pintype "passive"))
    )
    (net (code "16") (name "/P6V0_LDO") (class "Default")
      (node (ref "C337") (pin "2") (pinfunction "2_2") (pintype "passive"))
      (node (ref "C88") (pin "2") (pinfunction "2_2") (pintype "passive"))
      (node (ref "L13") (pin "2") (pinfunction "2_2") (pintype "passive"))
      (node (ref "L22") (pin "1") (pinfunction "1_1") (pintype "passive"))
      (node (ref "L23") (pin "1") (pinfunction "1_1") (pintype "passive"))
    )
    (net (code "17") (name "/P6V0_LDO_IN2") (class "Default")
      (node (ref "C339") (pin "2") (pinfunction "2_2") (pintype "passive"))
      (node (ref "IC22") (pin "1") (pinfunction "IN_1") (pintype "input"))
      (node (ref "IC22") (pin "2") (pinfunction "IN_2") (pintype "input"))
      (node (ref "IC22") (pin "6") (pinfunction "PGFB_6") (pintype "input"))
      (node (ref "L23") (pin "2") (pinfunction "2_2") (pintype "passive"))
    )
    (net (code "18") (name "/P6V0_LDO_IN3") (class "Default")
      (node (ref "C340") (pin "2") (pinfunction "2_2") (pintype "passive"))
      (node (ref "IC23") (pin "1") (pinfunction "IN_1") (pintype "input"))
      (node (ref "IC23") (pin "2") (pinfunction "IN_2") (pintype "input"))
      (node (ref "IC23") (pin "6") (pinfunction "PGFB_6") (pintype "input"))
      (node (ref "L22") (pin "2") (pinfunction "2_2") (pintype "passive"))
    )
    (net (code "19") (name "/REF0_LO_N") (class "Default")
      (node (ref "C224") (pin "2") (pinfunction "2_2") (pintype "passive"))
    )
    (net (code "20") (name "/REF0_LO_P") (class "Default")
      (node (ref "C227") (pin "2") (pinfunction "2_2") (pintype "passive"))
    )
    (net (code "21") (name "/REF1_LO_N") (class "Default")
      (node (ref "C225") (pin "2") (pinfunction "2_2") (pintype "passive"))
    )
    (net (code "22") (name "/REF1_LO_P") (class "Default")
      (node (ref "C226") (pin "2") (pinfunction "2_2") (pintype "passive"))
    )
    (net (code "23") (name "/REF2_N") (class "Default")
      (node (ref "C169") (pin "2") (pinfunction "2_2") (pintype "passive"))
    )
    (net (code "24") (name "/REF2_P") (class "Default")
      (node (ref "C168") (pin "2") (pinfunction "2_2") (pintype "passive"))
    )
    (net (code "25") (name "/REF_CLK_SRC_EXT_SEL") (class "Default")
      (node (ref "IC46") (pin "32") (pinfunction "IN_SEL_32") (pintype "input"))
      (node (ref "TP1") (pin "1") (pinfunction "1_1") (pintype "bidirectional"))
    )
    (net (code "26") (name "/REF_EXT_N") (class "Default")
      (node (ref "C111") (pin "2") (pinfunction "2_2") (pintype "passive"))
      (node (ref "J16") (pin "1") (pinfunction "1_1") (pintype "bidirectional"))
    )
    (net (code "27") (name "/REF_EXT_P") (class "Default")
      (node (ref "C113") (pin "2") (pinfunction "2_2") (pintype "passive"))
      (node (ref "J12") (pin "1") (pinfunction "1_1") (pintype "bidirectional"))
    )
    (net (code "28") (name "/REF_HMC_P") (class "Default")
      (node (ref "C148") (pin "1") (pinfunction "1_1") (pintype "passive"))
      (node (ref "IC46") (pin "14") (pinfunction "Q6_14") (pintype "output"))
      (node (ref "R102") (pin "1") (pinfunction "1_1") (pintype "passive"))
    )
    (net (code "29") (name "/RF_INOUT_N") (class "Default")
      (node (ref "C12") (pin "2") (pinfunction "2_2") (pintype "passive"))
      (node (ref "J10") (pin "1") (pinfunction "1_1") (pintype "bidirectional"))
    )
    (net (code "30") (name "/RF_INOUT_P") (class "Default")
      (node (ref "C11") (pin "2") (pinfunction "2_2") (pintype "passive"))
      (node (ref "J9") (pin "1") (pinfunction "1_1") (pintype "bidirectional"))
    )
    (net (code "31") (name "/RF_OUT_N") (class "Default")
      (node (ref "C12") (pin "1") (pinfunction "1_1") (pintype "passive"))
      (node (ref "C14") (pin "1") (pinfunction "1_1") (pintype "passive"))
    )
    (net (code "32") (name "/RF_OUT_P") (class "Default")
      (node (ref "C11") (pin "1") (pinfunction "1_1") (pintype "passive"))
      (node (ref "C13") (pin "1") (pinfunction "1_1") (pintype "passive"))
    )
    (net (code "33") (name "/VCCCP") (class "Default")
      (node (ref "C341") (pin "2") (pinfunction "2_2") (pintype "passive"))
      (node (ref "C85") (pin "2") (pinfunction "2_2") (pintype "passive"))
      (node (ref "C86") (pin "2") (pinfunction "2_2") (pintype "passive"))
      (node (ref "IC40") (pin "3") (pinfunction "VPPCP_3") (pintype "power_in"))
      (node (ref "IC40") (pin "7") (pinfunction "VDDLS_7") (pintype "power_in"))
      (node (ref "L39") (pin "1") (pinfunction "1_1") (pintype "passive"))
    )
    (net (code "34") (name "/VTUNE") (class "Default")
      (node (ref "IC40") (pin "21") (pinfunction "NC_21") (pintype "passive"))
      (node (ref "IC40") (pin "22") (pinfunction "NC_22") (pintype "passive"))
      (node (ref "IC40") (pin "23") (pinfunction "VTUNE_23") (pintype "input"))
      (node (ref "R148") (pin "1") (pinfunction "1_1") (pintype "passive"))
      (node (ref "R50") (pin "2") (pinfunction "2_2") (pintype "passive"))
      (node (ref "TP46") (pin "1") (pinfunction "1_1") (pintype "bidirectional"))
    )
    (net (code "37") (name "GND") (class "Default")
      (node (ref "C1") (pin "2") (pinfunction "2_2") (pintype "passive"))
      (node (ref "C10") (pin "1") (pinfunction "1_1") (pintype "passive"))
      (node (ref "C110") (pin "1") (pinfunction "1_1") (pintype "passive"))
      (node (ref "C140") (pin "1") (pinfunction "1_1") (pintype "passive"))
      (node (ref "C142") (pin "1") (pinfunction "1_1") (pintype "passive"))
      (node (ref "C144") (pin "1") (pinfunction "1_1") (pintype "passive"))
      (node (ref "C145") (pin "1") (pinfunction "1_1") (pintype "passive"))
      (node (ref "C146") (pin "1") (pinfunction "1_1") (pintype "passive"))
      (node (ref "C147") (pin "1") (pinfunction "1_1") (pintype "passive"))
      (node (ref "C15") (pin "1") (pinfunction "1_1") (pintype "passive"))
      (node (ref "C16") (pin "1") (pinfunction "1_1") (pintype "passive"))
      (node (ref "C2") (pin "1") (pinfunction "1_1") (pintype "passive"))
      (node (ref "C200") (pin "1") (pinfunction "1_1") (pintype "passive"))
      (node (ref "C202") (pin "1") (pinfunction "1_1") (pintype "passive"))
      (node (ref "C204") (pin "1") (pinfunction "1_1") (pintype "passive"))
      (node (ref "C210") (pin "1") (pinfunction "1_1") (pintype "passive"))
      (node (ref "C220") (pin "1") (pinfunction "1_1") (pintype "passive"))
      (node (ref "C221") (pin "1") (pinfunction "1_1") (pintype "passive"))
      (node (ref "C222") (pin "1") (pinfunction "1_1") (pintype "passive"))
      (node (ref "C223") (pin "1") (pinfunction "1_1") (pintype "passive"))
      (node (ref "C3") (pin "1") (pinfunction "1_1") (pintype "passive"))
      (node (ref "C335") (pin "1") (pinfunction "1_1") (pintype "passive"))
      (node (ref "C337") (pin "1") (pinfunction "1_1") (pintype "passive"))
      (node (ref "C338") (pin "1") (pinfunction "1_1") (pintype "passive"))
      (node (ref "C339") (pin "1") (pinfunction "1_1") (pintype "passive"))
      (node (ref "C340") (pin "1") (pinfunction "1_1") (pintype "passive"))
      (node (ref "C341") (pin "1") (pinfunction "1_1") (pintype "passive"))
      (node (ref "C4") (pin "1") (pinfunction "1_1") (pintype "passive"))
      (node (ref "C408") (pin "2") (pinfunction "2_2") (pintype "passive"))
      (node (ref "C409") (pin "1") (pinfunction "1_1") (pintype "passive"))
      (node (ref "C410") (pin "1") (pinfunction "1_1") (pintype "passive"))
      (node (ref "C471") (pin "2") (pinfunction "2_2") (pintype "passive"))
      (node (ref "C472") (pin "2") (pinfunction "2_2") (pintype "passive"))
      (node (ref "C5") (pin "1") (pinfunction "1_1") (pintype "passive"))
      (node (ref "C511") (pin "1") (pinfunction "1_1") (pintype "passive"))
      (node (ref "C512") (pin "1") (pinfunction "1_1") (pintype "passive"))
      (node (ref "C513") (pin "1") (pinfunction "1_1") (pintype "passive"))
      (node (ref "C552") (pin "1") (pinfunction "1_1") (pintype "passive"))
      (node (ref "C554") (pin "1") (pinfunction "1_1") (pintype "passive"))
      (node (ref "C85") (pin "1") (pinfunction "1_1") (pintype "passive"))
      (node (ref "C86") (pin "1") (pinfunction "1_1") (pintype "passive"))
      (node (ref "C88") (pin "1") (pinfunction "1_1") (pintype "passive"))
      (node (ref "C89") (pin "1") (pinfunction "1_1") (pintype "passive"))
      (node (ref "C9") (pin "1") (pinfunction "1_1") (pintype "passive"))
      (node (ref "C90") (pin "1") (pinfunction "1_1") (pintype "passive"))
      (node (ref "C91") (pin "1") (pinfunction "1_1") (pintype "passive"))
      (node (ref "C92") (pin "1") (pinfunction "1_1") (pintype "passive"))
      (node (ref "C93") (pin "1") (pinfunction "1_1") (pintype "passive"))
      (node (ref "C94") (pin "1") (pinfunction "1_1") (pintype "passive"))
      (node (ref "C95") (pin "1") (pinfunction "1_1") (pintype "passive"))
      (node (ref "IC16") (pin "4") (pinfunction "V-_4") (pintype "power_in"))
      (node (ref "IC22") (pin "11") (pinfunction "GND_11") (pintype "power_in"))
      (node (ref "IC22") (pin "5") (pinfunction "ILIM_5") (pintype "input"))
      (node (ref "IC22") (pin "8") (pinfunction "GND_8") (pintype "power_in"))
      (node (ref "IC23") (pin "11") (pinfunction "GND_11") (pintype "power_in"))
      (node (ref "IC23") (pin "5") (pinfunction "ILIM_5") (pintype "input"))
      (node (ref "IC23") (pin "8") (pinfunction "GND_8") (pintype "power_in"))
      (node (ref "IC40") (pin "41") (pinfunction "EP_41") (pintype "power_in"))
      (node (ref "IC40") (pin "5") (pinfunction "NC_5") (pintype "passive"))
      (node (ref "IC40") (pin "6") (pinfunction "NC_6") (pintype "passive"))
      (node (ref "IC46") (pin "33") (pinfunction "VEE_33") (pintype "power_in"))
      (node (ref "J10") (pin "2") (pinfunction "2_2") (pintype "bidirectional"))
      (node (ref "J12") (pin "2") (pinfunction "2_2") (pintype "bidirectional"))
      (node (ref "J16") (pin "2") (pinfunction "2_2") (pintype "bidirectional"))
      (node (ref "J9") (pin "2") (pinfunction "2_2") (pintype "bidirectional"))
      (node (ref "R107") (pin "1") (pinfunction "1_1") (pintype "passive"))
      (node (ref "R108") (pin "1") (pinfunction "1_1") (pintype "passive"))
      (node (ref "R109") (pin "2") (pinfunction "2_2") (pintype "passive"))
      (node (ref "R110") (pin "2") (pinfunction "2_2") (pintype "passive"))
      (node (ref "R111") (pin "2") (pinfunction "2_2") (pintype "passive"))
      (node (ref "R112") (pin "2") (pinfunction "2_2") (pintype "passive"))
      (node (ref "R128") (pin "2") (pinfunction "2_2") (pintype "passive"))
      (node (ref "R141") (pin "2") (pinfunction "2_2") (pintype "passive"))
      (node (ref "R177") (pin "2") (pinfunction "2_2") (pintype "passive"))
      (node (ref "R186") (pin "2") (pinfunction "2_2") (pintype "passive"))
      (node (ref "R204") (pin "1") (pinfunction "1_1") (pintype "passive"))
      (node (ref "R208") (pin "1") (pinfunction "1_1") (pintype "passive"))
      (node (ref "R59") (pin "2") (pinfunction "2_2") (pintype "passive"))
      (node (ref "R91") (pin "2") (pinfunction "2_2") (pintype "passive"))
      (node (ref "R95") (pin "1") (pinfunction "1_1") (pintype "passive"))
      (node (ref "SH1") (pin "1") (pinfunction "1_1") (pintype "passive"))
      (node (ref "SH1") (pin "10") (pinfunction "10_10") (pintype "passive"))
      (node (ref "SH1") (pin "11") (pinfunction "11_11") (pintype "passive"))
      (node (ref "SH1") (pin "12") (pinfunction "12_12") (pintype "passive"))
      (node (ref "SH1") (pin "13") (pinfunction "13_13") (pintype "passive"))
      (node (ref "SH1") (pin "14") (pinfunction "14_14") (pintype "passive"))
      (node (ref "SH1") (pin "15") (pinfunction "15_15") (pintype "passive"))
      (node (ref "SH1") (pin "16") (pinfunction "16_16") (pintype "passive"))
      (node (ref "SH1") (pin "17") (pinfunction "17_17") (pintype "passive"))
      (node (ref "SH1") (pin "18") (pinfunction "18_18") (pintype "passive"))
      (node (ref "SH1") (pin "19") (pinfunction "19_19") (pintype "passive"))
      (node (ref "SH1") (pin "2") (pinfunction "2_2") (pintype "passive"))
      (node (ref "SH1") (pin "20") (pinfunction "20_20") (pintype "passive"))
      (node (ref "SH1") (pin "3") (pinfunction "3_3") (pintype "passive"))
      (node (ref "SH1") (pin "4") (pinfunction "4_4") (pintype "passive"))
      (node (ref "SH1") (pin "5") (pinfunction "5_5") (pintype "passive"))
      (node (ref "SH1") (pin "6") (pinfunction "6_6") (pintype "passive"))
      (node (ref "SH1") (pin "7") (pinfunction "7_7") (pintype "passive"))
      (node (ref "SH1") (pin "8") (pinfunction "8_8") (pintype "passive"))
      (node (ref "SH1") (pin "9") (pinfunction "9_9") (pintype "passive"))
      (node (ref "T13") (pin "2") (pinfunction "S_2") (pintype "passive"))
      (node (ref "T14") (pin "2") (pinfunction "S_2") (pintype "passive"))
      (node (ref "T15") (pin "2") (pinfunction "S_2") (pintype "passive"))
      (node (ref "T16") (pin "2") (pinfunction "S_2") (pintype "passive"))
      (node (ref "TR1") (pin "5") (pinfunction "NC_5") (pintype "passive"))
    )
    (net (code "38") (name "Net-(C3-Pad2)") (class "Default")
      (node (ref "C3") (pin "2") (pinfunction "2_2") (pintype "passive"))
      (node (ref "C513") (pin "2") (pinfunction "2_2") (pintype "passive"))
      (node (ref "R139") (pin "2") (pinfunction "2_2") (pintype "passive"))
      (node (ref "R206") (pin "2") (pinfunction "2_2") (pintype "passive"))
      (node (ref "R207") (pin "2") (pinfunction "2_2") (pintype "passive"))
    )
    (net (code "39") (name "Net-(C4-Pad2)") (class "Default")
      (node (ref "C4") (pin "2") (pinfunction "2_2") (pintype "passive"))
      (node (ref "C511") (pin "2") (pinfunction "2_2") (pintype "passive"))
      (node (ref "R207") (pin "1") (pinfunction "1_1") (pintype "passive"))
      (node (ref "R50") (pin "1") (pinfunction "1_1") (pintype "passive"))
    )
    (net (code "40") (name "Net-(C10-Pad2)") (class "Default")
      (node (ref "C10") (pin "2") (pinfunction "2_2") (pintype "passive"))
      (node (ref "C201") (pin "1") (pinfunction "1_1") (pintype "passive"))
      (node (ref "TR1") (pin "4") (pinfunction "S1_4") (pintype "passive"))
    )
    (net (code "41") (name "Net-(C140-Pad2)") (class "Default")
      (node (ref "C140") (pin "2") (pinfunction "2_2") (pintype "passive"))
      (node (ref "C146") (pin "2") (pinfunction "2_2") (pintype "passive"))
      (node (ref "R138") (pin "1") (pinfunction "1_1") (pintype "passive"))
      (node (ref "R142") (pin "2") (pinfunction "2_2") (pintype "passive"))
    )
    (net (code "42") (name "Net-(C141-Pad2)") (class "Default")
      (node (ref "C141") (pin "2") (pinfunction "2_2") (pintype "passive"))
      (node (ref "R140") (pin "2") (pinfunction "2_2") (pintype "passive"))
    )
    (net (code "43") (name "Net-(C143-Pad2)") (class "Default")
      (node (ref "C143") (pin "2") (pinfunction "2_2") (pintype "passive"))
      (node (ref "R136") (pin "2") (pinfunction "2_2") (pintype "passive"))
    )
    (net (code "44") (name "Net-(C144-Pad2)") (class "Default")
      (node (ref "C144") (pin "2") (pinfunction "2_2") (pintype "passive"))
      (node (ref "C145") (pin "2") (pinfunction "2_2") (pintype "passive"))
      (node (ref "L56") (pin "2") (pinfunction "2_2") (pintype "passive"))
      (node (ref "R135") (pin "1") (pinfunction "1_1") (pintype "passive"))
    )
    (net (code "45") (name "Net-(C147-Pad2)") (class "Default")
      (node (ref "C147") (pin "2") (pinfunction "2_2") (pintype "passive"))
      (node (ref "L56") (pin "1") (pinfunction "1_1") (pintype "passive"))
      (node (ref "R148") (pin "2") (pinfunction "2_2") (pintype "passive"))
    )
    (net (code "46") (name "Net-(C168-Pad1)") (class "Default")
      (node (ref "C168") (pin "1") (pinfunction "1_1") (pintype "passive"))
      (node (ref "R92") (pin "2") (pinfunction "2_2") (pintype "passive"))
    )
    (net (code "47") (name "Net-(C169-Pad1)") (class "Default")
      (node (ref "C169") (pin "1") (pinfunction "1_1") (pintype "passive"))
      (node (ref "R178") (pin "2") (pinfunction "2_2") (pintype "passive"))
    )
    (net (code "48") (name "Net-(C200-Pad2)") (class "Default")
      (node (ref "C200") (pin "2") (pinfunction "2_2") (pintype "passive"))
      (node (ref "R97") (pin "1") (pinfunction "1_1") (pintype "passive"))
    )
    (net (code "49") (name "Net-(C203-Pad1)") (class "Default")
      (node (ref "C203") (pin "1") (pinfunction "1_1") (pintype "passive"))
      (node (ref "C9") (pin "2") (pinfunction "2_2") (pintype "passive"))
      (node (ref "TR1") (pin "6") (pinfunction "S1_6") (pintype "passive"))
    )
    (net (code "50") (name "Net-(C411-Pad2)") (class "Default")
      (node (ref "C411") (pin "2") (pinfunction "2_2") (pintype "passive"))
      (node (ref "TR1") (pin "3") (pinfunction "P1_3") (pintype "passive"))
    )
    (net (code "51") (name "Net-(C512-Pad2)") (class "Default")
      (node (ref "C512") (pin "2") (pinfunction "2_2") (pintype "passive"))
      (node (ref "C552") (pin "2") (pinfunction "2_2") (pintype "passive"))
      (node (ref "R206") (pin "1") (pinfunction "1_1") (pintype "passive"))
    )
    (net (code "52") (name "Net-(IC16-IN+)") (class "Default")
      (node (ref "C204") (pin "2") (pinfunction "2_2") (pintype "passive"))
      (node (ref "IC16") (pin "3") (pinfunction "IN+_3") (pintype "input"))
      (node (ref "R137") (pin "2") (pinfunction "2_2") (pintype "passive"))
      (node (ref "R141") (pin "1") (pinfunction "1_1") (pintype "passive"))
    )
    (net (code "53") (name "Net-(IC16-IN-)") (class "Default")
      (node (ref "IC16") (pin "2") (pinfunction "IN-_2") (pintype "input"))
      (node (ref "R136") (pin "1") (pinfunction "1_1") (pintype "passive"))
      (node (ref "R138") (pin "2") (pinfunction "2_2") (pintype "passive"))
      (node (ref "R140") (pin "1") (pinfunction "1_1") (pintype "passive"))
    )
    (net (code "54") (name "Net-(IC16-OUT)") (class "Default")
      (node (ref "C141") (pin "1") (pinfunction "1_1") (pintype "passive"))
      (node (ref "C143") (pin "1") (pinfunction "1_1") (pintype "passive"))
      (node (ref "IC16") (pin "6") (pinfunction "OUT_6") (pintype "output"))
      (node (ref "R135") (pin "2") (pinfunction "2_2") (pintype "passive"))
    )
    (net (code "55") (name "Net-(IC16-V+)") (class "Default")
      (node (ref "C142") (pin "2") (pinfunction "2_2") (pintype "passive"))
      (node (ref "IC16") (pin "7") (pinfunction "V+_7") (pintype "power_in"))
      (node (ref "L21") (pin "1") (pinfunction "1_1") (pintype "passive"))
      (node (ref "R137") (pin "1") (pinfunction "1_1") (pintype "passive"))
    )
    (net (code "56") (name "Net-(IC22-SET)") (class "Default")
      (node (ref "C472") (pin "1") (pinfunction "1_1") (pintype "passive"))
      (node (ref "IC22") (pin "7") (pinfunction "SET_7") (pintype "input"))
      (node (ref "R204") (pin "2") (pinfunction "2_2") (pintype "passive"))
    )
    (net (code "57") (name "Net-(IC23-SET)") (class "Default")
      (node (ref "C471") (pin "1") (pinfunction "1_1") (pintype "passive"))
      (node (ref "IC23") (pin "7") (pinfunction "SET_7") (pintype "input"))
      (node (ref "R208") (pin "2") (pinfunction "2_2") (pintype "passive"))
    )
    (net (code "58") (name "Net-(IC40-BIAS)") (class "Default")
      (node (ref "C87") (pin "1") (pinfunction "1_1") (pintype "passive"))
      (node (ref "IC40") (pin "40") (pinfunction "BIAS_40") (pintype "passive"))
    )
    (net (code "59") (name "Net-(IC40-CP)") (class "Default")
      (node (ref "IC40") (pin "4") (pinfunction "CP_4") (pintype "output"))
      (node (ref "R139") (pin "1") (pinfunction "1_1") (pintype "passive"))
      (node (ref "R142") (pin "1") (pinfunction "1_1") (pintype "passive"))
      (node (ref "TP57") (pin "1") (pinfunction "1_1") (pintype "bidirectional"))
    )
    (net (code "60") (name "Net-(IC40-DVDD3V)") (class "Default")
      (node (ref "C338") (pin "2") (pinfunction "2_2") (pintype "passive"))
      (node (ref "C91") (pin "2") (pinfunction "2_2") (pintype "passive"))
      (node (ref "IC40") (pin "16") (pinfunction "DVDD3V_16") (pintype "power_in"))
      (node (ref "R103") (pin "1") (pinfunction "1_1") (pintype "passive"))
    )
    (net (code "61") (name "Net-(IC40-RF_N)") (class "Default")
      (node (ref "C14") (pin "2") (pinfunction "2_2") (pintype "passive"))
      (node (ref "IC40") (pin "28") (pinfunction "RF_N_28") (pintype "output"))
    )
    (net (code "62") (name "Net-(IC40-RF_P)") (class "Default")
      (node (ref "C13") (pin "2") (pinfunction "2_2") (pintype "passive"))
      (node (ref "IC40") (pin "29") (pinfunction "RF_P_29") (pintype "output"))
    )
    (net (code "63") (name "Net-(IC40-XREFP)") (class "Default")
      (node (ref "C148") (pin "2") (pinfunction "2_2") (pintype "passive"))
      (node (ref "IC40") (pin "15") (pinfunction "XREFP_15") (pintype "input"))
      (node (ref "R97") (pin "2") (pinfunction "2_2") (pintype "passive"))
    )
    (net (code "64") (name "Net-(IC46-Q0)") (class "Default")
      (node (ref "C227") (pin "1") (pinfunction "1_1") (pintype "passive"))
      (node (ref "IC46") (pin "30") (pinfunction "Q0_30") (pintype "output"))
      (node (ref "R109") (pin "1") (pinfunction "1_1") (pintype "passive"))
    )
    (net (code "65") (name "Net-(IC46-Q1)") (class "Default")
      (node (ref "C226") (pin "1") (pinfunction "1_1") (pintype "passive"))
      (node (ref "IC46") (pin "28") (pinfunction "Q1_28") (pintype "output"))
      (node (ref "R111") (pin "1") (pinfunction "1_1") (pintype "passive"))
    )
    (net (code "66") (name "Net-(IC46-Q3)") (class "Default")
      (node (ref "C113") (pin "1") (pinfunction "1_1") (pintype "passive"))
      (node (ref "IC46") (pin "22") (pinfunction "Q3_22") (pintype "output"))
      (node (ref "R59") (pin "1") (pinfunction "1_1") (pintype "passive"))
    )
    (net (code "67") (name "Net-(IC46-Q5)") (class "Default")
      (node (ref "IC46") (pin "18") (pinfunction "Q5_18") (pintype "output"))
      (node (ref "R91") (pin "1") (pinfunction "1_1") (pintype "passive"))
      (node (ref "R92") (pin "1") (pinfunction "1_1") (pintype "passive"))
    )
    (net (code "68") (name "Net-(IC46-VREF0)") (class "Default")
      (node (ref "IC46") (pin "3") (pinfunction "VREF0_3") (pintype "input"))
      (node (ref "R104") (pin "1") (pinfunction "1_1") (pintype "passive"))
    )
    (net (code "69") (name "Net-(IC46-VREF1)") (class "Default")
      (node (ref "IC46") (pin "8") (pinfunction "VREF1_8") (pintype "input"))
      (node (ref "R105") (pin "1") (pinfunction "1_1") (pintype "passive"))
    )
    (net (code "70") (name "Net-(IC46-VT0)") (class "Default")
      (node (ref "C221") (pin "2") (pinfunction "2_2") (pintype "passive"))
      (node (ref "IC46") (pin "4") (pinfunction "VT0_4") (pintype "passive"))
      (node (ref "R104") (pin "2") (pinfunction "2_2") (pintype "passive"))
    )
    (net (code "71") (name "Net-(IC46-VT1)") (class "Default")
      (node (ref "C554") (pin "2") (pinfunction "2_2") (pintype "passive"))
      (node (ref "IC46") (pin "7") (pinfunction "VT1_7") (pintype "passive"))
      (node (ref "R105") (pin "2") (pinfunction "2_2") (pintype "passive"))
    )
    (net (code "72") (name "Net-(IC46-~{Q0})") (class "Default")
      (node (ref "C224") (pin "1") (pinfunction "1_1") (pintype "passive"))
      (node (ref "IC46") (pin "29") (pinfunction "~{Q0}_29") (pintype "output"))
      (node (ref "R110") (pin "1") (pinfunction "1_1") (pintype "passive"))
    )
    (net (code "73") (name "Net-(IC46-~{Q1})") (class "Default")
      (node (ref "C225") (pin "1") (pinfunction "1_1") (pintype "passive"))
      (node (ref "IC46") (pin "27") (pinfunction "~{Q1}_27") (pintype "output"))
      (node (ref "R112") (pin "1") (pinfunction "1_1") (pintype "passive"))
    )
    (net (code "74") (name "Net-(IC46-~{Q3})") (class "Default")
      (node (ref "C111") (pin "1") (pinfunction "1_1") (pintype "passive"))
      (node (ref "IC46") (pin "21") (pinfunction "~{Q3}_21") (pintype "output"))
      (node (ref "R128") (pin "1") (pinfunction "1_1") (pintype "passive"))
    )
    (net (code "75") (name "Net-(IC46-~{Q5})") (class "Default")
      (node (ref "IC46") (pin "17") (pinfunction "~{Q5}_17") (pintype "output"))
      (node (ref "R177") (pin "1") (pinfunction "1_1") (pintype "passive"))
      (node (ref "R178") (pin "1") (pinfunction "1_1") (pintype "passive"))
    )
    (net (code "76") (name "Net-(IC46-~{Q6})") (class "Default")
      (node (ref "IC46") (pin "13") (pinfunction "~{Q6}_13") (pintype "output"))
      (node (ref "R101") (pin "1") (pinfunction "1_1") (pintype "passive"))
    )
    (net (code "77") (name "Net-(T13-D)") (class "Default")
      (node (ref "C110") (pin "2") (pinfunction "2_2") (pintype "passive"))
      (node (ref "R101") (pin "2") (pinfunction "2_2") (pintype "passive"))
      (node (ref "R102") (pin "2") (pinfunction "2_2") (pintype "passive"))
      (node (ref "T13") (pin "3") (pinfunction "D_3") (pintype "passive"))
    )
    (net (code "78") (name "Net-(T14-D)") (class "Default")
      (node (ref "R75") (pin "1") (pinfunction "1_1") (pintype "passive"))
      (node (ref "T14") (pin "3") (pinfunction "D_3") (pintype "passive"))
    )
    (net (code "79") (name "Net-(T14-G)") (class "Default")
      (node (ref "R127") (pin "1") (pinfunction "1_1") (pintype "passive"))
      (node (ref "T14") (pin "1") (pinfunction "G_1") (pintype "passive"))
      (node (ref "T15") (pin "1") (pinfunction "G_1") (pintype "passive"))
      (node (ref "T16") (pin "3") (pinfunction "D_3") (pintype "passive"))
    )
    (net (code "80") (name "Net-(T15-D)") (class "Default")
      (node (ref "R76") (pin "1") (pinfunction "1_1") (pintype "passive"))
      (node (ref "T15") (pin "3") (pinfunction "D_3") (pintype "passive"))
    )
    (net (code "81") (name "P3V3_CLKDIS1") (class "Default")
      (node (ref "L24") (pin "1") (pinfunction "1_1") (pintype "passive"))
    )
    (net (code "82") (name "P3V3_HMC") (class "Default")
      (node (ref "C335") (pin "2") (pinfunction "2_2") (pintype "passive"))
      (node (ref "C5") (pin "2") (pinfunction "2_2") (pintype "passive"))
      (node (ref "C87") (pin "2") (pinfunction "2_2") (pintype "passive"))
      (node (ref "C89") (pin "2") (pinfunction "2_2") (pintype "passive"))
      (node (ref "C90") (pin "2") (pinfunction "2_2") (pintype "passive"))
      (node (ref "C92") (pin "2") (pinfunction "2_2") (pintype "passive"))
      (node (ref "C93") (pin "2") (pinfunction "2_2") (pintype "passive"))
      (node (ref "C94") (pin "2") (pinfunction "2_2") (pintype "passive"))
      (node (ref "C95") (pin "2") (pinfunction "2_2") (pintype "passive"))
      (node (ref "IC23") (pin "10") (pinfunction "OUT_10") (pintype "output"))
      (node (ref "IC23") (pin "9") (pinfunction "OUTS_9") (pintype "output"))
      (node (ref "IC40") (pin "1") (pinfunction "AVDD_1") (pintype "power_in"))
      (node (ref "IC40") (pin "10") (pinfunction "RVDD_10") (pintype "power_in"))
      (node (ref "IC40") (pin "17") (pinfunction "CEN_17") (pintype "input"))
      (node (ref "IC40") (pin "18") (pinfunction "NC_18") (pintype "passive"))
      (node (ref "IC40") (pin "19") (pinfunction "NC_19") (pintype "passive"))
      (node (ref "IC40") (pin "20") (pinfunction "NC_20") (pintype "passive"))
      (node (ref "IC40") (pin "35") (pinfunction "VCCHF_35") (pintype "power_in"))
      (node (ref "IC40") (pin "36") (pinfunction "VCCPS_36") (pintype "power_in"))
      (node (ref "IC40") (pin "39") (pinfunction "VCCPD_39") (pintype "power_in"))
      (node (ref "R103") (pin "2") (pinfunction "2_2") (pintype "passive"))
      (node (ref "R76") (pin "2") (pinfunction "2_2") (pintype "passive"))
      (node (ref "TP75") (pin "1") (pinfunction "1_1") (pintype "bidirectional"))
    )
    (net (code "83") (name "P5V0_HMC") (class "Default")
      (node (ref "C2") (pin "2") (pinfunction "2_2") (pintype "passive"))
      (node (ref "IC22") (pin "10") (pinfunction "OUT_10") (pintype "output"))
      (node (ref "IC22") (pin "9") (pinfunction "OUTS_9") (pintype "output"))
      (node (ref "L21") (pin "2") (pinfunction "2_2") (pintype "passive"))
      (node (ref "L37") (pin "2") (pinfunction "2_2") (pintype "passive"))
      (node (ref "L39") (pin "2") (pinfunction "2_2") (pintype "passive"))
      (node (ref "R75") (pin "2") (pinfunction "2_2") (pintype "passive"))
      (node (ref "TP74") (pin "1") (pinfunction "1_1") (pintype "bidirectional"))
    )
    (net (code "84") (name "P6V0A") (class "Default")
      (node (ref "L13") (pin "1") (pinfunction "1_1") (pintype "passive"))
      (node (ref "R127") (pin "2") (pinfunction "2_2") (pintype "passive"))
    )
    (net (code "85") (name "unconnected-(IC22-PG-Pad4)") (class "Default")
      (node (ref "IC22") (pin "4") (pinfunction "PG_4") (pintype "output+no_connect"))
    )
    (net (code "86") (name "unconnected-(IC23-PG-Pad4)") (class "Default")
      (node (ref "IC23") (pin "4") (pinfunction "PG_4") (pintype "output+no_connect"))
    )
    (net (code "87") (name "unconnected-(IC40-NC-Pad2)") (class "Default")
      (node (ref "IC40") (pin "2") (pinfunction "NC_2") (pintype "passive+no_connect"))
    )
    (net (code "88") (name "unconnected-(IC40-NC-Pad8)") (class "Default")
      (node (ref "IC40") (pin "8") (pinfunction "NC_8") (pintype "passive+no_connect"))
    )
    (net (code "89") (name "unconnected-(IC40-NC-Pad9)") (class "Default")
      (node (ref "IC40") (pin "9") (pinfunction "NC_9") (pintype "passive+no_connect"))
    )
    (net (code "90") (name "unconnected-(IC40-NC-Pad11)") (class "Default")
      (node (ref "IC40") (pin "11") (pinfunction "NC_11") (pintype "passive+no_connect"))
    )
    (net (code "91") (name "unconnected-(IC40-NC-Pad12)") (class "Default")
      (node (ref "IC40") (pin "12") (pinfunction "NC_12") (pintype "passive+no_connect"))
    )
    (net (code "92") (name "unconnected-(IC40-NC-Pad13)") (class "Default")
      (node (ref "IC40") (pin "13") (pinfunction "NC_13") (pintype "passive+no_connect"))
    )
    (net (code "93") (name "unconnected-(IC40-NC-Pad14)") (class "Default")
      (node (ref "IC40") (pin "14") (pinfunction "NC_14") (pintype "passive+no_connect"))
    )
    (net (code "94") (name "unconnected-(IC40-NC-Pad34)") (class "Default")
      (node (ref "IC40") (pin "34") (pinfunction "NC_34") (pintype "passive+no_connect"))
    )
    (net (code "95") (name "unconnected-(IC40-NC-Pad37)") (class "Default")
      (node (ref "IC40") (pin "37") (pinfunction "NC_37") (pintype "passive+no_connect"))
    )
    (net (code "96") (name "unconnected-(IC40-NC-Pad38)") (class "Default")
      (node (ref "IC40") (pin "38") (pinfunction "NC_38") (pintype "passive+no_connect"))
    )
    (net (code "97") (name "unconnected-(IC46-NC-Pad9)") (class "Default")
      (node (ref "IC46") (pin "9") (pinfunction "NC_9") (pintype "passive+no_connect"))
    )
    (net (code "98") (name "unconnected-(IC46-Q2-Pad24)") (class "Default")
      (node (ref "IC46") (pin "24") (pinfunction "Q2_24") (pintype "output"))
    )
    (net (code "99") (name "unconnected-(IC46-Q4-Pad20)") (class "Default")
      (node (ref "IC46") (pin "20") (pinfunction "Q4_20") (pintype "output"))
    )
    (net (code "100") (name "unconnected-(IC46-Q7-Pad12)") (class "Default")
      (node (ref "IC46") (pin "12") (pinfunction "Q7_12") (pintype "output"))
    )
    (net (code "101") (name "unconnected-(IC46-~{Q2}-Pad23)") (class "Default")
      (node (ref "IC46") (pin "23") (pinfunction "~{Q2}_23") (pintype "output"))
    )
    (net (code "102") (name "unconnected-(IC46-~{Q4}-Pad19)") (class "Default")
      (node (ref "IC46") (pin "19") (pinfunction "~{Q4}_19") (pintype "output"))
    )
    (net (code "103") (name "unconnected-(IC46-~{Q7}-Pad11)") (class "Default")
      (node (ref "IC46") (pin "11") (pinfunction "~{Q7}_11") (pintype "output"))
    )
  )
)
